# new_board.net
KiCad netlist of a schematic drawn in Altium Designer
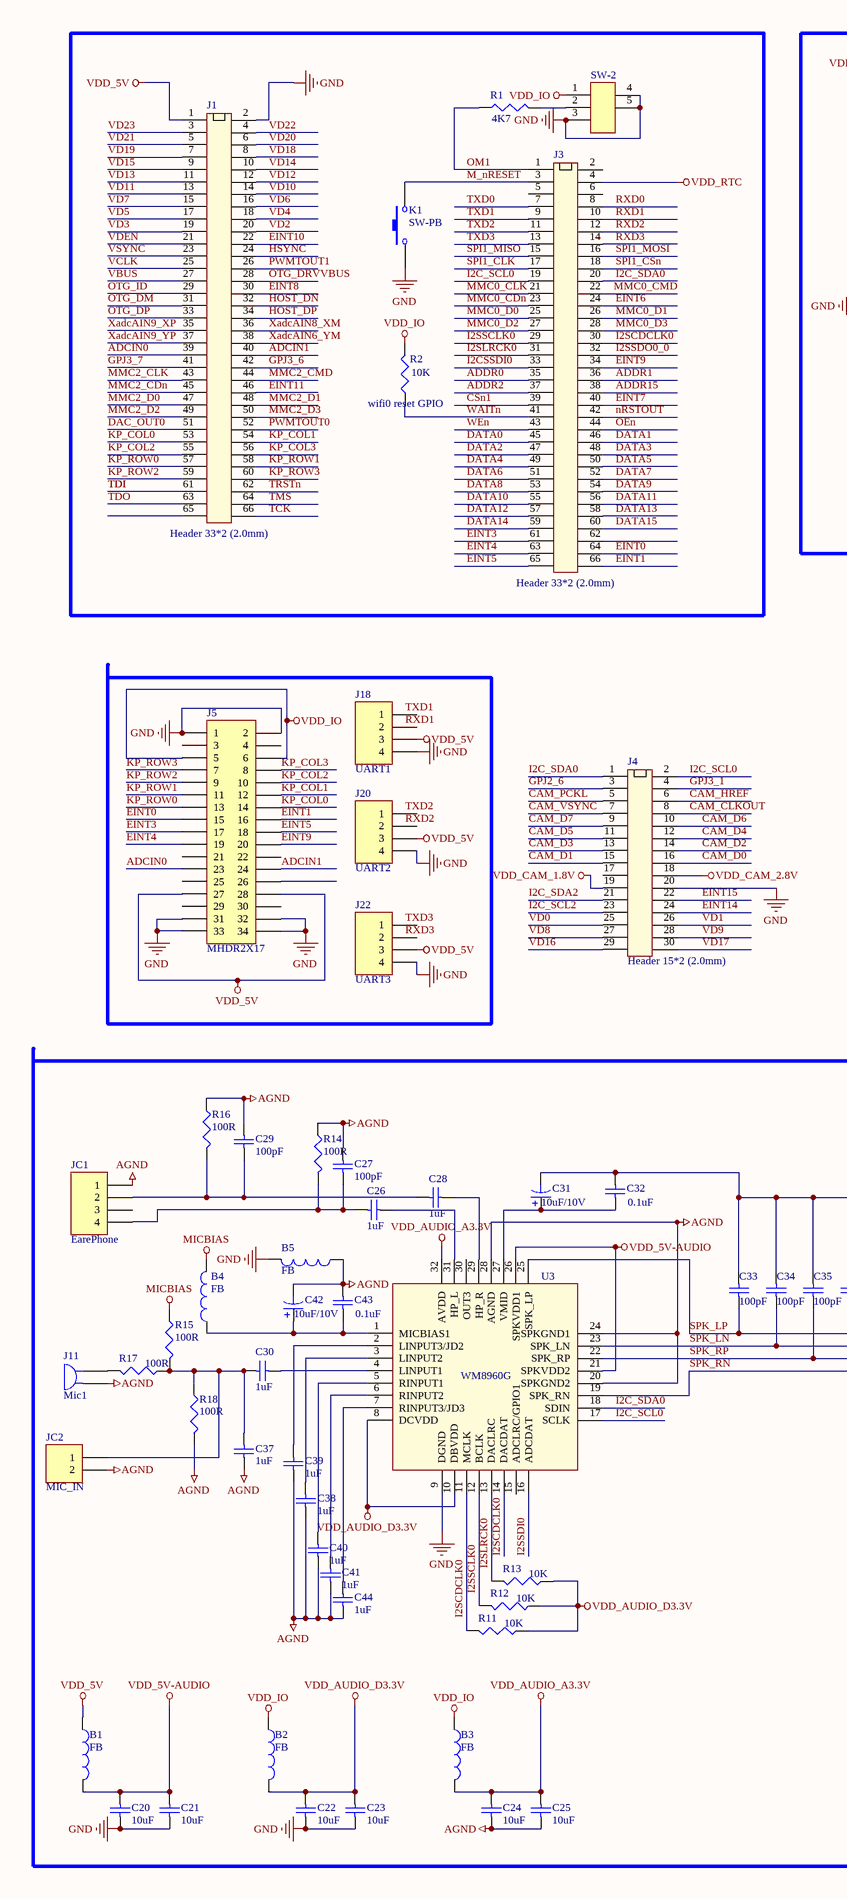
[diagram p0: new_board.SchDoc, left]
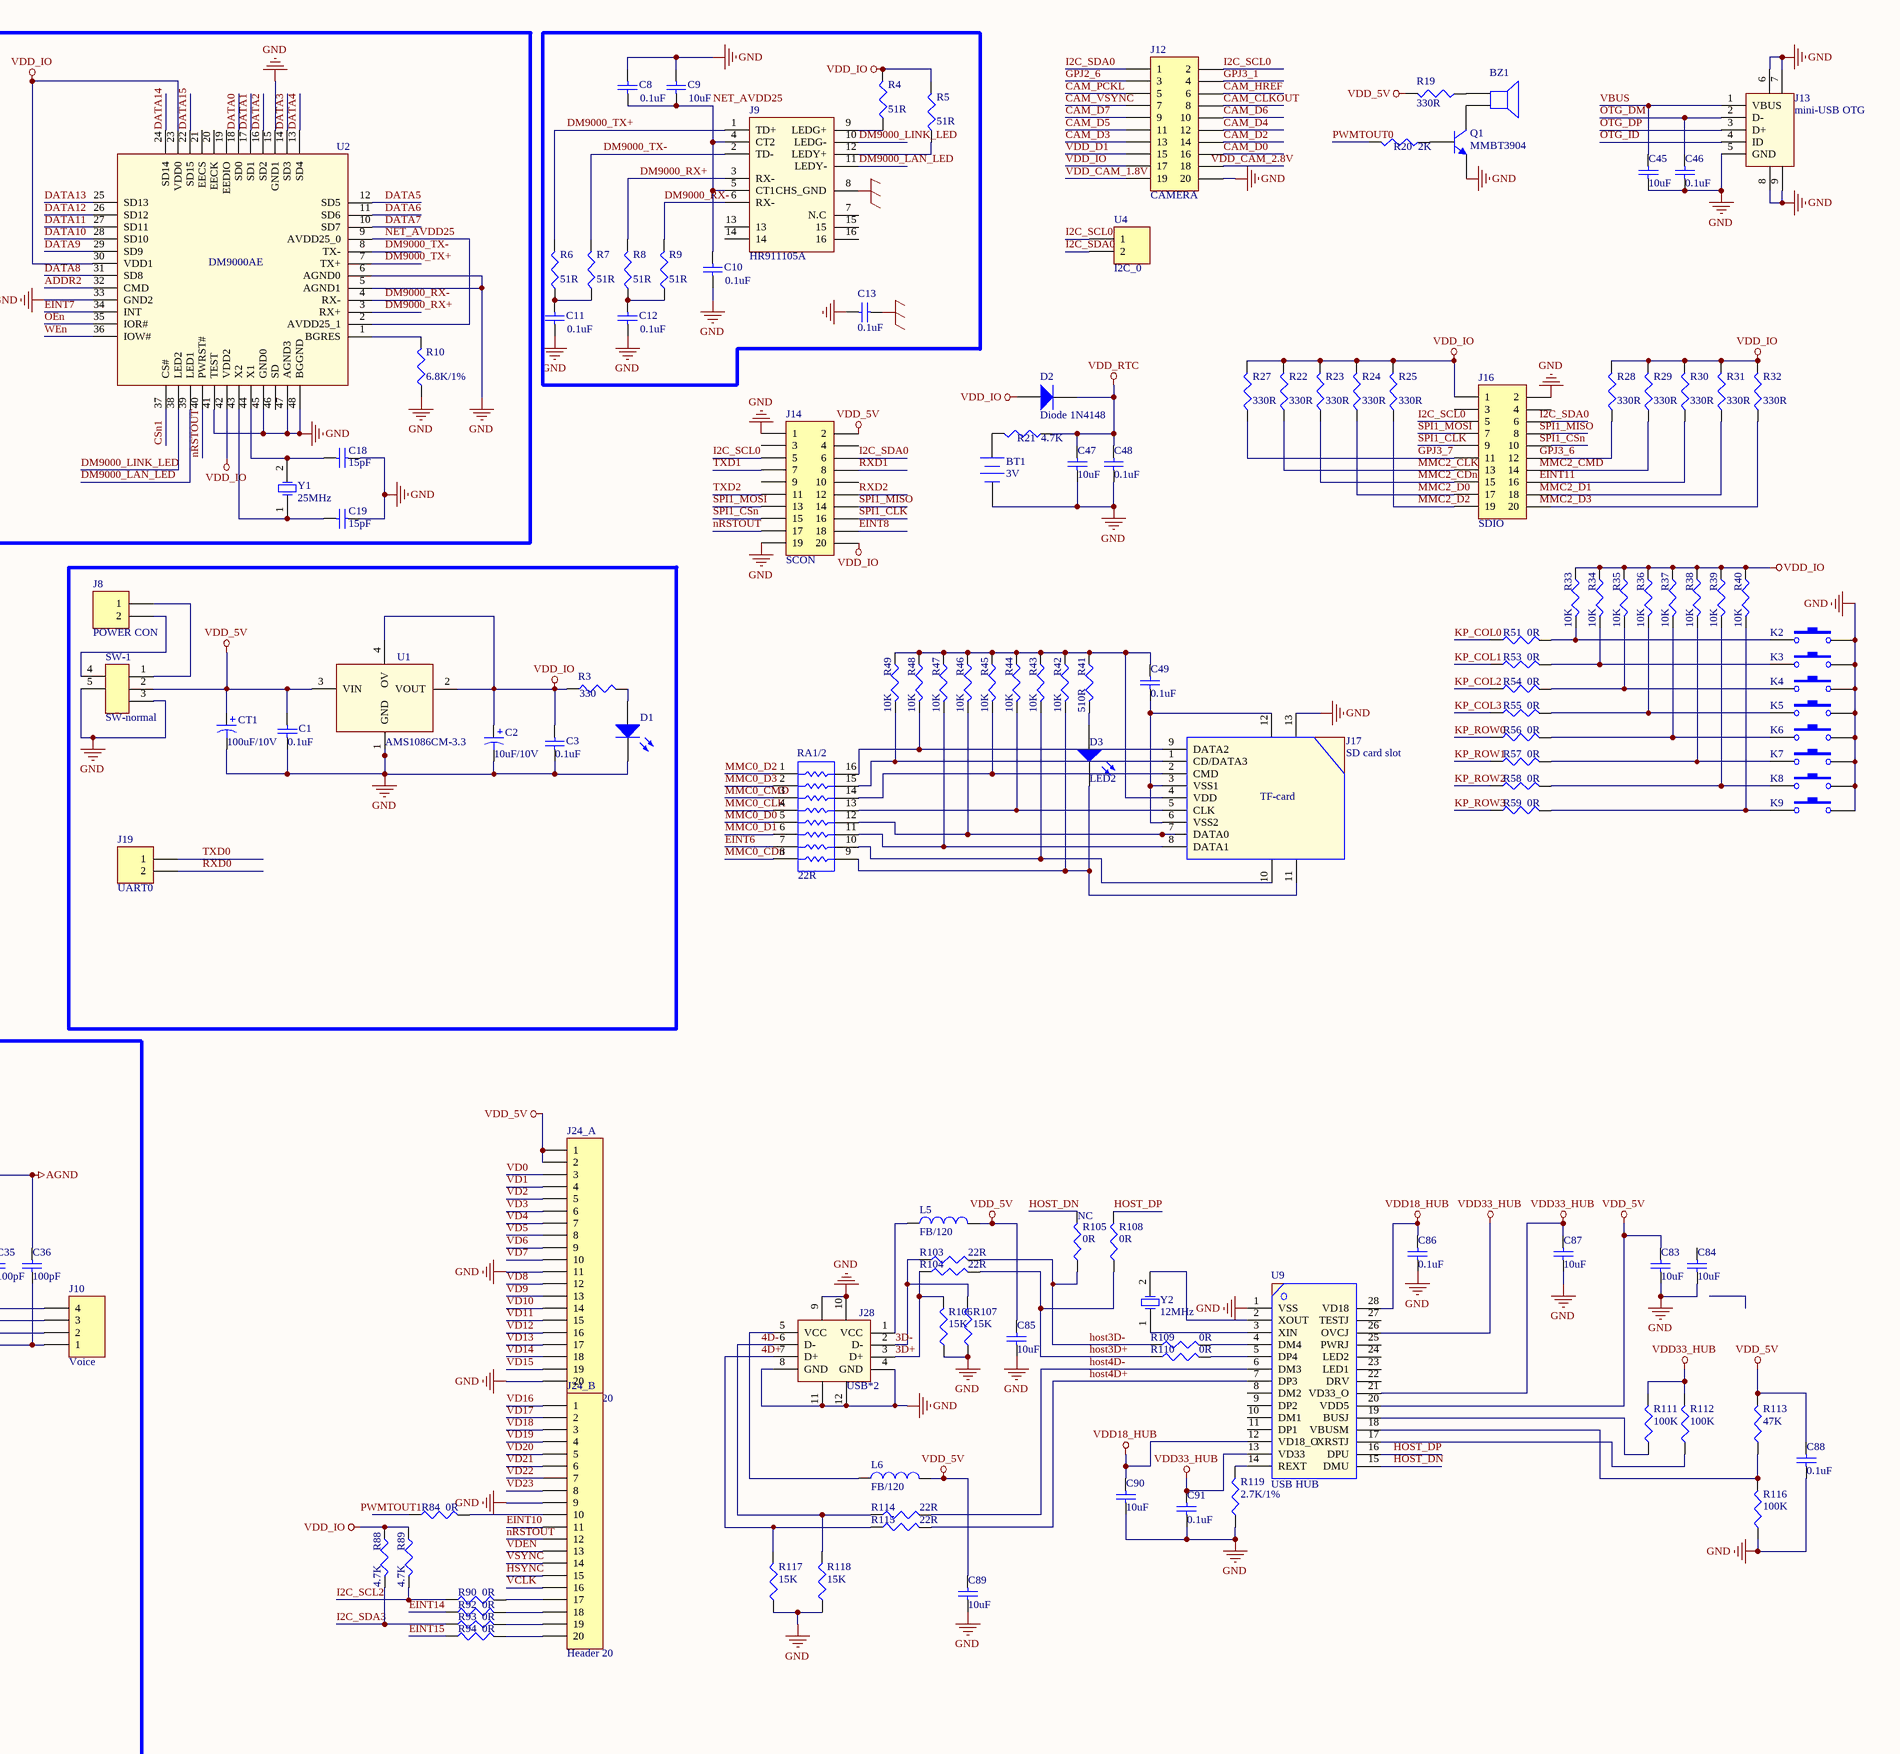
[diagram p1: new_board.SchDoc, right]

(export (version "E")
  (design (tool "Eeschema 10.0.6"))
  (components
    (comp (ref "B1")
      (value "FB")
      (footprint "0603")
      (description "Inductor")
      (fields (field (name "PUBLISHER") "Altium Limited"))
      (libsource (lib "Miscellaneous Devices") (part "Inductor"))
    )
    (comp (ref "B2")
      (value "FB")
      (footprint "0603")
      (description "Inductor")
      (fields (field (name "PUBLISHER") "Altium Limited"))
      (libsource (lib "Miscellaneous Devices") (part "Inductor"))
    )
    (comp (ref "B3")
      (value "FB")
      (footprint "0603")
      (description "Inductor")
      (fields (field (name "PUBLISHER") "Altium Limited"))
      (libsource (lib "Miscellaneous Devices") (part "Inductor"))
    )
    (comp (ref "B4")
      (value "FB")
      (footprint "0603")
      (description "Inductor")
      (fields (field (name "PUBLISHER") "Altium Limited"))
      (libsource (lib "Miscellaneous Devices") (part "Inductor"))
    )
    (comp (ref "B5")
      (value "FB")
      (footprint "0603")
      (description "Inductor")
      (fields (field (name "PUBLISHER") "Altium Limited"))
      (libsource (lib "Miscellaneous Devices") (part "Inductor"))
    )
    (comp (ref "BT1")
      (value "3V")
      (footprint "BAT-2")
      (description "Multicell Battery")
      (fields (field (name "PUBLISHER") "Altium Limited"))
      (libsource (lib "Miscellaneous Devices") (part "Battery"))
    )
    (comp (ref "BZ1")
      (value "Speaker")
      (footprint "PIN2")
      (description "Loudspeaker")
      (fields (field (name "PUBLISHER") "Altium Limited"))
      (libsource (lib "Miscellaneous Devices") (part "Speaker"))
    )
    (comp (ref "C1")
      (value "0.1uF")
      (footprint "1608[0603]")
      (description "Capacitor (Semiconductor SIM Model)")
      (fields (field (name "Comment") "Cap Semi") (field (name "PUBLISHER") "Altium Limited"))
      (libsource (lib "Miscellaneous Devices") (part "Cap Semi"))
    )
    (comp (ref "C2")
      (value "10uF/10V")
      (footprint "C0805")
      (description "Polarized Capacitor (Surface Mount)")
      (fields (field (name "Comment") "Cap Pol3") (field (name "PUBLISHER") "Altium Limited"))
      (libsource (lib "Miscellaneous Devices") (part "Cap Pol3"))
    )
    (comp (ref "C3")
      (value "0.1uF")
      (footprint "1608[0603]")
      (description "Capacitor (Semiconductor SIM Model)")
      (fields (field (name "Comment") "Cap Semi") (field (name "PUBLISHER") "Altium Limited"))
      (libsource (lib "Miscellaneous Devices") (part "Cap Semi"))
    )
    (comp (ref "C8")
      (value "0.1uF")
      (footprint "1608[0603]")
      (description "Capacitor (Semiconductor SIM Model)")
      (fields (field (name "Comment") "Cap Semi") (field (name "PUBLISHER") "Altium Limited"))
      (libsource (lib "Miscellaneous Devices") (part "Cap Semi"))
    )
    (comp (ref "C9")
      (value "10uF")
      (footprint "1608[0603]")
      (description "Capacitor (Semiconductor SIM Model)")
      (fields (field (name "Comment") "Cap Semi") (field (name "PUBLISHER") "Altium Limited"))
      (libsource (lib "Miscellaneous Devices") (part "Cap Semi"))
    )
    (comp (ref "C10")
      (value "0.1uF")
      (footprint "1608[0603]")
      (description "Capacitor (Semiconductor SIM Model)")
      (fields (field (name "Comment") "Cap Semi") (field (name "PUBLISHER") "Altium Limited"))
      (libsource (lib "Miscellaneous Devices") (part "Cap Semi"))
    )
    (comp (ref "C11")
      (value "0.1uF")
      (footprint "1608[0603]")
      (description "Capacitor (Semiconductor SIM Model)")
      (fields (field (name "Comment") "Cap Semi") (field (name "PUBLISHER") "Altium Limited"))
      (libsource (lib "Miscellaneous Devices") (part "Cap Semi"))
    )
    (comp (ref "C12")
      (value "0.1uF")
      (footprint "1608[0603]")
      (description "Capacitor (Semiconductor SIM Model)")
      (fields (field (name "Comment") "Cap Semi") (field (name "PUBLISHER") "Altium Limited"))
      (libsource (lib "Miscellaneous Devices") (part "Cap Semi"))
    )
    (comp (ref "C13")
      (value "0.1uF")
      (footprint "1608[0603]")
      (description "Capacitor (Semiconductor SIM Model)")
      (fields (field (name "Comment") "Cap Semi") (field (name "PUBLISHER") "Altium Limited"))
      (libsource (lib "Miscellaneous Devices") (part "Cap Semi"))
    )
    (comp (ref "C18")
      (value "15pF")
      (footprint "1608[0603]")
      (description "Capacitor (Semiconductor SIM Model)")
      (fields (field (name "Comment") "Cap Semi") (field (name "PUBLISHER") "Altium Limited"))
      (libsource (lib "Miscellaneous Devices") (part "Cap Semi"))
    )
    (comp (ref "C19")
      (value "15pF")
      (footprint "1608[0603]")
      (description "Capacitor (Semiconductor SIM Model)")
      (fields (field (name "Comment") "Cap Semi") (field (name "PUBLISHER") "Altium Limited"))
      (libsource (lib "Miscellaneous Devices") (part "Cap Semi"))
    )
    (comp (ref "C20")
      (value "10uF")
      (footprint "1608[0603]")
      (description "Capacitor (Semiconductor SIM Model)")
      (fields (field (name "Comment") "Cap Semi") (field (name "PUBLISHER") "Altium Limited"))
      (libsource (lib "Miscellaneous Devices") (part "Cap Semi"))
    )
    (comp (ref "C21")
      (value "10uF")
      (footprint "1608[0603]")
      (description "Capacitor (Semiconductor SIM Model)")
      (fields (field (name "Comment") "Cap Semi") (field (name "PUBLISHER") "Altium Limited"))
      (libsource (lib "Miscellaneous Devices") (part "Cap Semi"))
    )
    (comp (ref "C22")
      (value "10uF")
      (footprint "1608[0603]")
      (description "Capacitor (Semiconductor SIM Model)")
      (fields (field (name "Comment") "Cap Semi") (field (name "PUBLISHER") "Altium Limited"))
      (libsource (lib "Miscellaneous Devices") (part "Cap Semi"))
    )
    (comp (ref "C23")
      (value "10uF")
      (footprint "1608[0603]")
      (description "Capacitor (Semiconductor SIM Model)")
      (fields (field (name "Comment") "Cap Semi") (field (name "PUBLISHER") "Altium Limited"))
      (libsource (lib "Miscellaneous Devices") (part "Cap Semi"))
    )
    (comp (ref "C24")
      (value "10uF")
      (footprint "1608[0603]")
      (description "Capacitor (Semiconductor SIM Model)")
      (fields (field (name "Comment") "Cap Semi") (field (name "PUBLISHER") "Altium Limited"))
      (libsource (lib "Miscellaneous Devices") (part "Cap Semi"))
    )
    (comp (ref "C25")
      (value "10uF")
      (footprint "1608[0603]")
      (description "Capacitor (Semiconductor SIM Model)")
      (fields (field (name "Comment") "Cap Semi") (field (name "PUBLISHER") "Altium Limited"))
      (libsource (lib "Miscellaneous Devices") (part "Cap Semi"))
    )
    (comp (ref "C26")
      (value "1uF")
      (footprint "1608[0603]")
      (description "Capacitor (Semiconductor SIM Model)")
      (fields (field (name "Comment") "Cap Semi") (field (name "PUBLISHER") "Altium Limited"))
      (libsource (lib "Miscellaneous Devices") (part "Cap Semi"))
    )
    (comp (ref "C27")
      (value "100pF")
      (footprint "1608[0603]")
      (description "Capacitor (Semiconductor SIM Model)")
      (fields (field (name "Comment") "Cap Semi") (field (name "PUBLISHER") "Altium Limited"))
      (libsource (lib "Miscellaneous Devices") (part "Cap Semi"))
    )
    (comp (ref "C28")
      (value "1uF")
      (footprint "1608[0603]")
      (description "Capacitor (Semiconductor SIM Model)")
      (fields (field (name "Comment") "Cap Semi") (field (name "PUBLISHER") "Altium Limited"))
      (libsource (lib "Miscellaneous Devices") (part "Cap Semi"))
    )
    (comp (ref "C29")
      (value "100pF")
      (footprint "1608[0603]")
      (description "Capacitor (Semiconductor SIM Model)")
      (fields (field (name "Comment") "Cap Semi") (field (name "PUBLISHER") "Altium Limited"))
      (libsource (lib "Miscellaneous Devices") (part "Cap Semi"))
    )
    (comp (ref "C30")
      (value "1uF")
      (footprint "1608[0603]")
      (description "Capacitor (Semiconductor SIM Model)")
      (fields (field (name "Comment") "Cap Semi") (field (name "PUBLISHER") "Altium Limited"))
      (libsource (lib "Miscellaneous Devices") (part "Cap Semi"))
    )
    (comp (ref "C31")
      (value "10uF/10V")
      (footprint "C0805")
      (description "Polarized Capacitor (Surface Mount)")
      (fields (field (name "Comment") "Cap Pol3") (field (name "PUBLISHER") "Altium Limited"))
      (libsource (lib "Miscellaneous Devices") (part "Cap Pol3"))
    )
    (comp (ref "C32")
      (value "0.1uF")
      (footprint "1608[0603]")
      (description "Capacitor (Semiconductor SIM Model)")
      (fields (field (name "Comment") "Cap Semi") (field (name "PUBLISHER") "Altium Limited"))
      (libsource (lib "Miscellaneous Devices") (part "Cap Semi"))
    )
    (comp (ref "C33")
      (value "100pF")
      (footprint "1608[0603]")
      (description "Capacitor (Semiconductor SIM Model)")
      (fields (field (name "Comment") "Cap Semi") (field (name "PUBLISHER") "Altium Limited"))
      (libsource (lib "Miscellaneous Devices") (part "Cap Semi"))
    )
    (comp (ref "C34")
      (value "100pF")
      (footprint "1608[0603]")
      (description "Capacitor (Semiconductor SIM Model)")
      (fields (field (name "Comment") "Cap Semi") (field (name "PUBLISHER") "Altium Limited"))
      (libsource (lib "Miscellaneous Devices") (part "Cap Semi"))
    )
    (comp (ref "C35")
      (value "100pF")
      (footprint "1608[0603]")
      (description "Capacitor (Semiconductor SIM Model)")
      (fields (field (name "Comment") "Cap Semi") (field (name "PUBLISHER") "Altium Limited"))
      (libsource (lib "Miscellaneous Devices") (part "Cap Semi"))
    )
    (comp (ref "C36")
      (value "100pF")
      (footprint "1608[0603]")
      (description "Capacitor (Semiconductor SIM Model)")
      (fields (field (name "Comment") "Cap Semi") (field (name "PUBLISHER") "Altium Limited"))
      (libsource (lib "Miscellaneous Devices") (part "Cap Semi"))
    )
    (comp (ref "C37")
      (value "1uF")
      (footprint "1608[0603]")
      (description "Capacitor (Semiconductor SIM Model)")
      (fields (field (name "Comment") "Cap Semi") (field (name "PUBLISHER") "Altium Limited"))
      (libsource (lib "Miscellaneous Devices") (part "Cap Semi"))
    )
    (comp (ref "C38")
      (value "1uF")
      (footprint "1608[0603]")
      (description "Capacitor (Semiconductor SIM Model)")
      (fields (field (name "Comment") "Cap Semi") (field (name "PUBLISHER") "Altium Limited"))
      (libsource (lib "Miscellaneous Devices") (part "Cap Semi"))
    )
    (comp (ref "C39")
      (value "1uF")
      (footprint "1608[0603]")
      (description "Capacitor (Semiconductor SIM Model)")
      (fields (field (name "Comment") "Cap Semi") (field (name "PUBLISHER") "Altium Limited"))
      (libsource (lib "Miscellaneous Devices") (part "Cap Semi"))
    )
    (comp (ref "C40")
      (value "1uF")
      (footprint "1608[0603]")
      (description "Capacitor (Semiconductor SIM Model)")
      (fields (field (name "Comment") "Cap Semi") (field (name "PUBLISHER") "Altium Limited"))
      (libsource (lib "Miscellaneous Devices") (part "Cap Semi"))
    )
    (comp (ref "C41")
      (value "1uF")
      (footprint "1608[0603]")
      (description "Capacitor (Semiconductor SIM Model)")
      (fields (field (name "Comment") "Cap Semi") (field (name "PUBLISHER") "Altium Limited"))
      (libsource (lib "Miscellaneous Devices") (part "Cap Semi"))
    )
    (comp (ref "C42")
      (value "10uF/10V")
      (footprint "C0805")
      (description "Polarized Capacitor (Surface Mount)")
      (fields (field (name "Comment") "Cap Pol3") (field (name "PUBLISHER") "Altium Limited"))
      (libsource (lib "Miscellaneous Devices") (part "Cap Pol3"))
    )
    (comp (ref "C43")
      (value "0.1uF")
      (footprint "1608[0603]")
      (description "Capacitor (Semiconductor SIM Model)")
      (fields (field (name "Comment") "Cap Semi") (field (name "PUBLISHER") "Altium Limited"))
      (libsource (lib "Miscellaneous Devices") (part "Cap Semi"))
    )
    (comp (ref "C44")
      (value "1uF")
      (footprint "1608[0603]")
      (description "Capacitor (Semiconductor SIM Model)")
      (fields (field (name "Comment") "Cap Semi") (field (name "PUBLISHER") "Altium Limited"))
      (libsource (lib "Miscellaneous Devices") (part "Cap Semi"))
    )
    (comp (ref "C45")
      (value "10uF")
      (footprint "1608[0603]")
      (description "Capacitor (Semiconductor SIM Model)")
      (fields (field (name "Comment") "Cap Semi") (field (name "PUBLISHER") "Altium Limited"))
      (libsource (lib "Miscellaneous Devices") (part "Cap Semi"))
    )
    (comp (ref "C46")
      (value "0.1uF")
      (footprint "1608[0603]")
      (description "Capacitor (Semiconductor SIM Model)")
      (fields (field (name "Comment") "Cap Semi") (field (name "PUBLISHER") "Altium Limited"))
      (libsource (lib "Miscellaneous Devices") (part "Cap Semi"))
    )
    (comp (ref "C47")
      (value "10uF")
      (footprint "1608[0603]")
      (description "Capacitor (Semiconductor SIM Model)")
      (fields (field (name "Comment") "Cap Semi") (field (name "PUBLISHER") "Altium Limited"))
      (libsource (lib "Miscellaneous Devices") (part "Cap Semi"))
    )
    (comp (ref "C48")
      (value "0.1uF")
      (footprint "1608[0603]")
      (description "Capacitor (Semiconductor SIM Model)")
      (fields (field (name "Comment") "Cap Semi") (field (name "PUBLISHER") "Altium Limited"))
      (libsource (lib "Miscellaneous Devices") (part "Cap Semi"))
    )
    (comp (ref "C49")
      (value "0.1uF")
      (footprint "1608[0603]")
      (description "Capacitor (Semiconductor SIM Model)")
      (fields (field (name "Comment") "Cap Semi") (field (name "PUBLISHER") "Altium Limited"))
      (libsource (lib "Miscellaneous Devices") (part "Cap Semi"))
    )
    (comp (ref "C83")
      (value "10uF")
      (footprint "1608[0603]")
      (description "Capacitor (Semiconductor SIM Model)")
      (fields (field (name "Comment") "Cap Semi") (field (name "PUBLISHER") "Altium Limited"))
      (libsource (lib "Miscellaneous Devices") (part "Cap Semi"))
    )
    (comp (ref "C84")
      (value "10uF")
      (footprint "1608[0603]")
      (description "Capacitor (Semiconductor SIM Model)")
      (fields (field (name "Comment") "Cap Semi") (field (name "PUBLISHER") "Altium Limited"))
      (libsource (lib "Miscellaneous Devices") (part "Cap Semi"))
    )
    (comp (ref "C85")
      (value "10uF")
      (footprint "1608[0603]")
      (description "Capacitor (Semiconductor SIM Model)")
      (fields (field (name "Comment") "Cap Semi") (field (name "PUBLISHER") "Altium Limited"))
      (libsource (lib "Miscellaneous Devices") (part "Cap Semi"))
    )
    (comp (ref "C86")
      (value "0.1uF")
      (footprint "1608[0603]")
      (description "Capacitor (Semiconductor SIM Model)")
      (fields (field (name "Comment") "Cap Semi") (field (name "PUBLISHER") "Altium Limited"))
      (libsource (lib "Miscellaneous Devices") (part "Cap Semi"))
    )
    (comp (ref "C87")
      (value "10uF")
      (footprint "1608[0603]")
      (description "Capacitor (Semiconductor SIM Model)")
      (fields (field (name "Comment") "Cap Semi") (field (name "PUBLISHER") "Altium Limited"))
      (libsource (lib "Miscellaneous Devices") (part "Cap Semi"))
    )
    (comp (ref "C88")
      (value "0.1uF")
      (footprint "1608[0603]")
      (description "Capacitor (Semiconductor SIM Model)")
      (fields (field (name "Comment") "Cap Semi") (field (name "PUBLISHER") "Altium Limited"))
      (libsource (lib "Miscellaneous Devices") (part "Cap Semi"))
    )
    (comp (ref "C89")
      (value "10uF")
      (footprint "1608[0603]")
      (description "Capacitor (Semiconductor SIM Model)")
      (fields (field (name "Comment") "Cap Semi") (field (name "PUBLISHER") "Altium Limited"))
      (libsource (lib "Miscellaneous Devices") (part "Cap Semi"))
    )
    (comp (ref "C90")
      (value "10uF")
      (footprint "1608[0603]")
      (description "Capacitor (Semiconductor SIM Model)")
      (fields (field (name "Comment") "Cap Semi") (field (name "PUBLISHER") "Altium Limited"))
      (libsource (lib "Miscellaneous Devices") (part "Cap Semi"))
    )
    (comp (ref "C91")
      (value "0.1uF")
      (footprint "1608[0603]")
      (description "Capacitor (Semiconductor SIM Model)")
      (fields (field (name "Comment") "Cap Semi") (field (name "PUBLISHER") "Altium Limited"))
      (libsource (lib "Miscellaneous Devices") (part "Cap Semi"))
    )
    (comp (ref "CT1")
      (value "100uF/10V")
      (footprint "C0805")
      (description "Polarized Capacitor (Surface Mount)")
      (fields (field (name "Comment") "Cap Pol3") (field (name "PUBLISHER") "Altium Limited"))
      (libsource (lib "Miscellaneous Devices") (part "Cap Pol3"))
    )
    (comp (ref "D1")
      (value "LED1")
      (footprint "3.2X1.6X1.1")
      (description "Typical RED, GREEN, YELLOW, AMBER GaAs LED")
      (fields (field (name "PUBLISHER") "Altium Limited"))
      (libsource (lib "Miscellaneous Devices") (part "LED2"))
    )
    (comp (ref "D2")
      (value "Diode 1N4148")
      (footprint "DO-35")
      (description "High Conductance Fast Diode")
      (fields (field (name "PUBLISHER") "Altium Limited"))
      (libsource (lib "Miscellaneous Devices") (part "Diode 1N4148"))
    )
    (comp (ref "D3")
      (value "LED2")
      (footprint "3.2X1.6X1.1")
      (description "Typical RED, GREEN, YELLOW, AMBER GaAs LED")
      (fields (field (name "PUBLISHER") "Altium Limited"))
      (libsource (lib "Miscellaneous Devices") (part "LED2"))
    )
    (comp (ref "J1") (value "Header 33*2 (2.0mm)") (libsource (lib "Schlib") (part "Header 33*2 (2.0mm)")))
    (comp (ref "J3") (value "Header 33*2 (2.0mm)") (libsource (lib "Schlib") (part "Header 33*2 (2.0mm)")))
    (comp (ref "J4") (value "Header 15*2 (2.0mm)") (libsource (lib "Schlib") (part "Header 15*2 (2.0mm)")))
    (comp (ref "J5")
      (value "MHDR2X17")
      (footprint "MHDR2X17")
      (description "Header, 17-Pin, Dual row")
      (fields (field (name "PUBLISHER") "Altium Limited"))
      (libsource (lib "Miscellaneous Connectors") (part "MHDR2X17"))
    )
    (comp (ref "J8")
      (value "POWER CON")
      (footprint "HDR1X2H")
      (description "Header, 2-Pin, Right Angle")
      (fields (field (name "PUBLISHER") "Altium Limited"))
      (libsource (lib "Miscellaneous Connectors") (part "Header 2H"))
    )
    (comp (ref "J9")
      (value "HR911105A")
      (description "100M net connector")
      (libsource (lib "Schlib") (part "HR911105A"))
    )
    (comp (ref "J10")
      (value "Voice")
      (footprint "HDR1X4")
      (description "Header, 4-Pin")
      (fields (field (name "PUBLISHER") "Altium Limited"))
      (libsource (lib "") (part "Header 4_1"))
    )
    (comp (ref "J11")
      (value "Mic1")
      (footprint "PIN2")
      (description "Microphone")
      (fields (field (name "PUBLISHER") "Altium Limited"))
      (libsource (lib "Miscellaneous Devices") (part "Mic1"))
    )
    (comp (ref "J12")
      (value "CAMERA")
      (footprint "HDR2X10")
      (description "Header, 10-Pin, Dual row")
      (fields (field (name "PUBLISHER") "Altium Limited"))
      (libsource (lib "Miscellaneous Connectors") (part "Header 10X2"))
    )
    (comp (ref "J13") (value "mini-USB OTG") (libsource (lib "Schlib") (part "mini-USB OTG")))
    (comp (ref "J14")
      (value "SCON")
      (footprint "HDR2X10")
      (description "Header, 10-Pin, Dual row")
      (fields (field (name "PUBLISHER") "Altium Limited"))
      (libsource (lib "Miscellaneous Connectors") (part "Header 10X2"))
    )
    (comp (ref "J16")
      (value "SDIO")
      (footprint "HDR2X10")
      (description "Header, 10-Pin, Dual row")
      (fields (field (name "PUBLISHER") "Altium Limited"))
      (libsource (lib "Miscellaneous Connectors") (part "Header 10X2"))
    )
    (comp (ref "J17") (value "SD card slot") (libsource (lib "Schlib") (part "SD card slot")))
    (comp (ref "J18")
      (value "UART1")
      (footprint "MHDR1X4")
      (description "Header, 4-Pin")
      (fields (field (name "PUBLISHER") "Altium Limited"))
      (libsource (lib "Miscellaneous Connectors") (part "MHDR1X4"))
    )
    (comp (ref "J19")
      (value "UART0")
      (footprint "HDR1X2H")
      (description "Header, 2-Pin, Right Angle")
      (fields (field (name "PUBLISHER") "Altium Limited"))
      (libsource (lib "Miscellaneous Connectors") (part "Header 2H"))
    )
    (comp (ref "J20")
      (value "UART2")
      (footprint "MHDR1X4")
      (description "Header, 4-Pin")
      (fields (field (name "PUBLISHER") "Altium Limited"))
      (libsource (lib "Miscellaneous Connectors") (part "MHDR1X4"))
    )
    (comp (ref "J22")
      (value "UART3")
      (footprint "MHDR1X4")
      (description "Header, 4-Pin")
      (fields (field (name "PUBLISHER") "Altium Limited"))
      (libsource (lib "Miscellaneous Connectors") (part "MHDR1X4"))
    )
    (comp (ref "J24_A")
      (value "Header 20")
      (footprint "HDR1X20")
      (description "Header, 20-Pin")
      (fields (field (name "PUBLISHER") "Altium Limited"))
      (libsource (lib "Miscellaneous Connectors") (part "Header 20"))
    )
    (comp (ref "J24_B")
      (value "Header 20")
      (footprint "HDR1X20")
      (description "Header, 20-Pin")
      (fields (field (name "PUBLISHER") "Altium Limited"))
      (libsource (lib "Miscellaneous Connectors") (part "Header 20"))
    )
    (comp (ref "J28") (value "USB*2") (libsource (lib "Schlib") (part "USB*2")))
    (comp (ref "JC1")
      (value "EarePhone")
      (footprint "HDR1X4")
      (description "Header, 4-Pin")
      (fields (field (name "PUBLISHER") "Altium Limited"))
      (libsource (lib "Miscellaneous Connectors") (part "Header 4"))
    )
    (comp (ref "JC2")
      (value "MIC_IN")
      (footprint "HDR1X2")
      (description "Header, 2-Pin")
      (fields (field (name "PUBLISHER") "Altium Limited"))
      (libsource (lib "") (part "Header 2_1"))
    )
    (comp (ref "K1")
      (value "SW-PB")
      (footprint "SPST-2")
      (description "Switch")
      (fields (field (name "PUBLISHER") "Altium Limited"))
      (libsource (lib "Miscellaneous Devices") (part "SW-PB"))
    )
    (comp (ref "K2")
      (value "SW-PB")
      (footprint "SPST-2")
      (description "Switch")
      (fields (field (name "PUBLISHER") "Altium Limited"))
      (libsource (lib "Miscellaneous Devices") (part "SW-PB"))
    )
    (comp (ref "K3")
      (value "SW-PB")
      (footprint "SPST-2")
      (description "Switch")
      (fields (field (name "PUBLISHER") "Altium Limited"))
      (libsource (lib "Miscellaneous Devices") (part "SW-PB"))
    )
    (comp (ref "K4")
      (value "SW-PB")
      (footprint "SPST-2")
      (description "Switch")
      (fields (field (name "PUBLISHER") "Altium Limited"))
      (libsource (lib "Miscellaneous Devices") (part "SW-PB"))
    )
    (comp (ref "K5")
      (value "SW-PB")
      (footprint "SPST-2")
      (description "Switch")
      (fields (field (name "PUBLISHER") "Altium Limited"))
      (libsource (lib "Miscellaneous Devices") (part "SW-PB"))
    )
    (comp (ref "K6")
      (value "SW-PB")
      (footprint "SPST-2")
      (description "Switch")
      (fields (field (name "PUBLISHER") "Altium Limited"))
      (libsource (lib "Miscellaneous Devices") (part "SW-PB"))
    )
    (comp (ref "K7")
      (value "SW-PB")
      (footprint "SPST-2")
      (description "Switch")
      (fields (field (name "PUBLISHER") "Altium Limited"))
      (libsource (lib "Miscellaneous Devices") (part "SW-PB"))
    )
    (comp (ref "K8")
      (value "SW-PB")
      (footprint "SPST-2")
      (description "Switch")
      (fields (field (name "PUBLISHER") "Altium Limited"))
      (libsource (lib "Miscellaneous Devices") (part "SW-PB"))
    )
    (comp (ref "K9")
      (value "SW-PB")
      (footprint "SPST-2")
      (description "Switch")
      (fields (field (name "PUBLISHER") "Altium Limited"))
      (libsource (lib "Miscellaneous Devices") (part "SW-PB"))
    )
    (comp (ref "L5")
      (value "FB/120")
      (footprint "0603")
      (description "Inductor")
      (fields (field (name "PUBLISHER") "Altium Limited"))
      (libsource (lib "Miscellaneous Devices") (part "Inductor"))
    )
    (comp (ref "L6")
      (value "FB/120")
      (footprint "0603")
      (description "Inductor")
      (fields (field (name "PUBLISHER") "Altium Limited"))
      (libsource (lib "Miscellaneous Devices") (part "Inductor"))
    )
    (comp (ref "Q1")
      (value "MMBT3904")
      (footprint "SOT-23B_N")
      (description "NPN Bipolar Transistor")
      (fields (field (name "PUBLISHER") "Altium Limited"))
      (libsource (lib "Miscellaneous Devices") (part "QNPN"))
    )
    (comp (ref "R1")
      (value "4K7")
      (footprint "J1-0603")
      (description "Resistor")
      (fields (field (name "Comment") "Res3") (field (name "PUBLISHER") "Altium Limited"))
      (libsource (lib "Miscellaneous Devices") (part "Res3"))
    )
    (comp (ref "R2")
      (value "10K")
      (footprint "J1-0603")
      (description "Resistor")
      (fields (field (name "Comment") "Res3") (field (name "PUBLISHER") "Altium Limited"))
      (libsource (lib "Miscellaneous Devices") (part "Res3"))
    )
    (comp (ref "R3")
      (value "330")
      (footprint "J1-0603")
      (description "Resistor")
      (fields (field (name "Comment") "Res3") (field (name "PUBLISHER") "Altium Limited"))
      (libsource (lib "Miscellaneous Devices") (part "Res3"))
    )
    (comp (ref "R4")
      (value "51R")
      (footprint "J1-0603")
      (description "Resistor")
      (fields (field (name "Comment") "Res3") (field (name "PUBLISHER") "Altium Limited"))
      (libsource (lib "Miscellaneous Devices") (part "Res3"))
    )
    (comp (ref "R5")
      (value "51R")
      (footprint "J1-0603")
      (description "Resistor")
      (fields (field (name "Comment") "Res3") (field (name "PUBLISHER") "Altium Limited"))
      (libsource (lib "Miscellaneous Devices") (part "Res3"))
    )
    (comp (ref "R6")
      (value "51R")
      (footprint "J1-0603")
      (description "Resistor")
      (fields (field (name "Comment") "Res3") (field (name "PUBLISHER") "Altium Limited"))
      (libsource (lib "Miscellaneous Devices") (part "Res3"))
    )
    (comp (ref "R7")
      (value "51R")
      (footprint "J1-0603")
      (description "Resistor")
      (fields (field (name "Comment") "Res3") (field (name "PUBLISHER") "Altium Limited"))
      (libsource (lib "Miscellaneous Devices") (part "Res3"))
    )
    (comp (ref "R8")
      (value "51R")
      (footprint "J1-0603")
      (description "Resistor")
      (fields (field (name "Comment") "Res3") (field (name "PUBLISHER") "Altium Limited"))
      (libsource (lib "Miscellaneous Devices") (part "Res3"))
    )
    (comp (ref "R9")
      (value "51R")
      (footprint "J1-0603")
      (description "Resistor")
      (fields (field (name "Comment") "Res3") (field (name "PUBLISHER") "Altium Limited"))
      (libsource (lib "Miscellaneous Devices") (part "Res3"))
    )
    (comp (ref "R10")
      (value "6.8K/1%")
      (footprint "J1-0603")
      (description "Resistor")
      (fields (field (name "Comment") "Res3") (field (name "PUBLISHER") "Altium Limited"))
      (libsource (lib "Miscellaneous Devices") (part "Res3"))
    )
    (comp (ref "R11")
      (value "10K")
      (footprint "J1-0603")
      (description "Resistor")
      (fields (field (name "Comment") "Res3") (field (name "PUBLISHER") "Altium Limited"))
      (libsource (lib "Miscellaneous Devices") (part "Res3"))
    )
    (comp (ref "R12")
      (value "10K")
      (footprint "J1-0603")
      (description "Resistor")
      (fields (field (name "Comment") "Res3") (field (name "PUBLISHER") "Altium Limited"))
      (libsource (lib "Miscellaneous Devices") (part "Res3"))
    )
    (comp (ref "R13")
      (value "10K")
      (footprint "J1-0603")
      (description "Resistor")
      (fields (field (name "Comment") "Res3") (field (name "PUBLISHER") "Altium Limited"))
      (libsource (lib "Miscellaneous Devices") (part "Res3"))
    )
    (comp (ref "R14")
      (value "100R")
      (footprint "J1-0603")
      (description "Resistor")
      (fields (field (name "Comment") "Res3") (field (name "PUBLISHER") "Altium Limited"))
      (libsource (lib "Miscellaneous Devices") (part "Res3"))
    )
    (comp (ref "R15")
      (value "100R")
      (footprint "J1-0603")
      (description "Resistor")
      (fields (field (name "Comment") "Res3") (field (name "PUBLISHER") "Altium Limited"))
      (libsource (lib "Miscellaneous Devices") (part "Res3"))
    )
    (comp (ref "R16")
      (value "100R")
      (footprint "J1-0603")
      (description "Resistor")
      (fields (field (name "Comment") "Res3") (field (name "PUBLISHER") "Altium Limited"))
      (libsource (lib "Miscellaneous Devices") (part "Res3"))
    )
    (comp (ref "R17")
      (value "100R")
      (footprint "J1-0603")
      (description "Resistor")
      (fields (field (name "Comment") "Res3") (field (name "PUBLISHER") "Altium Limited"))
      (libsource (lib "Miscellaneous Devices") (part "Res3"))
    )
    (comp (ref "R18")
      (value "100R")
      (footprint "J1-0603")
      (description "Resistor")
      (fields (field (name "Comment") "Res3") (field (name "PUBLISHER") "Altium Limited"))
      (libsource (lib "Miscellaneous Devices") (part "Res3"))
    )
    (comp (ref "R19")
      (value "330R")
      (footprint "J1-0603")
      (description "Resistor")
      (fields (field (name "Comment") "Res3") (field (name "PUBLISHER") "Altium Limited"))
      (libsource (lib "Miscellaneous Devices") (part "Res3"))
    )
    (comp (ref "R20")
      (value "2K")
      (footprint "J1-0603")
      (description "Resistor")
      (fields (field (name "Comment") "Res3") (field (name "PUBLISHER") "Altium Limited"))
      (libsource (lib "Miscellaneous Devices") (part "Res3"))
    )
    (comp (ref "R21")
      (value "4.7K")
      (footprint "J1-0603")
      (description "Resistor")
      (fields (field (name "Comment") "Res3") (field (name "PUBLISHER") "Altium Limited"))
      (libsource (lib "Miscellaneous Devices") (part "Res3"))
    )
    (comp (ref "R22")
      (value "330R")
      (footprint "J1-0603")
      (description "Resistor")
      (fields (field (name "Comment") "Res3") (field (name "PUBLISHER") "Altium Limited"))
      (libsource (lib "Miscellaneous Devices") (part "Res3"))
    )
    (comp (ref "R23")
      (value "330R")
      (footprint "J1-0603")
      (description "Resistor")
      (fields (field (name "Comment") "Res3") (field (name "PUBLISHER") "Altium Limited"))
      (libsource (lib "Miscellaneous Devices") (part "Res3"))
    )
    (comp (ref "R24")
      (value "330R")
      (footprint "J1-0603")
      (description "Resistor")
      (fields (field (name "Comment") "Res3") (field (name "PUBLISHER") "Altium Limited"))
      (libsource (lib "Miscellaneous Devices") (part "Res3"))
    )
    (comp (ref "R25")
      (value "330R")
      (footprint "J1-0603")
      (description "Resistor")
      (fields (field (name "Comment") "Res3") (field (name "PUBLISHER") "Altium Limited"))
      (libsource (lib "Miscellaneous Devices") (part "Res3"))
    )
    (comp (ref "R27")
      (value "330R")
      (footprint "J1-0603")
      (description "Resistor")
      (fields (field (name "Comment") "Res3") (field (name "PUBLISHER") "Altium Limited"))
      (libsource (lib "Miscellaneous Devices") (part "Res3"))
    )
    (comp (ref "R28")
      (value "330R")
      (footprint "J1-0603")
      (description "Resistor")
      (fields (field (name "Comment") "Res3") (field (name "PUBLISHER") "Altium Limited"))
      (libsource (lib "Miscellaneous Devices") (part "Res3"))
    )
    (comp (ref "R29")
      (value "330R")
      (footprint "J1-0603")
      (description "Resistor")
      (fields (field (name "Comment") "Res3") (field (name "PUBLISHER") "Altium Limited"))
      (libsource (lib "Miscellaneous Devices") (part "Res3"))
    )
    (comp (ref "R30")
      (value "330R")
      (footprint "J1-0603")
      (description "Resistor")
      (fields (field (name "Comment") "Res3") (field (name "PUBLISHER") "Altium Limited"))
      (libsource (lib "Miscellaneous Devices") (part "Res3"))
    )
    (comp (ref "R31")
      (value "330R")
      (footprint "J1-0603")
      (description "Resistor")
      (fields (field (name "Comment") "Res3") (field (name "PUBLISHER") "Altium Limited"))
      (libsource (lib "Miscellaneous Devices") (part "Res3"))
    )
    (comp (ref "R32")
      (value "330R")
      (footprint "J1-0603")
      (description "Resistor")
      (fields (field (name "Comment") "Res3") (field (name "PUBLISHER") "Altium Limited"))
      (libsource (lib "Miscellaneous Devices") (part "Res3"))
    )
    (comp (ref "R33")
      (value "10K")
      (footprint "J1-0603")
      (description "Resistor")
      (fields (field (name "Comment") "Res3") (field (name "PUBLISHER") "Altium Limited"))
      (libsource (lib "Miscellaneous Devices") (part "Res3"))
    )
    (comp (ref "R34")
      (value "10K")
      (footprint "J1-0603")
      (description "Resistor")
      (fields (field (name "Comment") "Res3") (field (name "PUBLISHER") "Altium Limited"))
      (libsource (lib "Miscellaneous Devices") (part "Res3"))
    )
    (comp (ref "R35")
      (value "10K")
      (footprint "J1-0603")
      (description "Resistor")
      (fields (field (name "Comment") "Res3") (field (name "PUBLISHER") "Altium Limited"))
      (libsource (lib "Miscellaneous Devices") (part "Res3"))
    )
    (comp (ref "R36")
      (value "10K")
      (footprint "J1-0603")
      (description "Resistor")
      (fields (field (name "Comment") "Res3") (field (name "PUBLISHER") "Altium Limited"))
      (libsource (lib "Miscellaneous Devices") (part "Res3"))
    )
    (comp (ref "R37")
      (value "10K")
      (footprint "J1-0603")
      (description "Resistor")
      (fields (field (name "Comment") "Res3") (field (name "PUBLISHER") "Altium Limited"))
      (libsource (lib "Miscellaneous Devices") (part "Res3"))
    )
    (comp (ref "R38")
      (value "10K")
      (footprint "J1-0603")
      (description "Resistor")
      (fields (field (name "Comment") "Res3") (field (name "PUBLISHER") "Altium Limited"))
      (libsource (lib "Miscellaneous Devices") (part "Res3"))
    )
    (comp (ref "R39")
      (value "10K")
      (footprint "J1-0603")
      (description "Resistor")
      (fields (field (name "Comment") "Res3") (field (name "PUBLISHER") "Altium Limited"))
      (libsource (lib "Miscellaneous Devices") (part "Res3"))
    )
    (comp (ref "R40")
      (value "10K")
      (footprint "J1-0603")
      (description "Resistor")
      (fields (field (name "Comment") "Res3") (field (name "PUBLISHER") "Altium Limited"))
      (libsource (lib "Miscellaneous Devices") (part "Res3"))
    )
    (comp (ref "R41")
      (value "510R")
      (footprint "J1-0603")
      (description "Resistor")
      (fields (field (name "Comment") "Res3") (field (name "PUBLISHER") "Altium Limited"))
      (libsource (lib "Miscellaneous Devices") (part "Res3"))
    )
    (comp (ref "R42")
      (value "10K")
      (footprint "J1-0603")
      (description "Resistor")
      (fields (field (name "Comment") "Res3") (field (name "PUBLISHER") "Altium Limited"))
      (libsource (lib "Miscellaneous Devices") (part "Res3"))
    )
    (comp (ref "R43")
      (value "10K")
      (footprint "J1-0603")
      (description "Resistor")
      (fields (field (name "Comment") "Res3") (field (name "PUBLISHER") "Altium Limited"))
      (libsource (lib "Miscellaneous Devices") (part "Res3"))
    )
    (comp (ref "R44")
      (value "10K")
      (footprint "J1-0603")
      (description "Resistor")
      (fields (field (name "Comment") "Res3") (field (name "PUBLISHER") "Altium Limited"))
      (libsource (lib "Miscellaneous Devices") (part "Res3"))
    )
    (comp (ref "R45")
      (value "10K")
      (footprint "J1-0603")
      (description "Resistor")
      (fields (field (name "Comment") "Res3") (field (name "PUBLISHER") "Altium Limited"))
      (libsource (lib "Miscellaneous Devices") (part "Res3"))
    )
    (comp (ref "R46")
      (value "10K")
      (footprint "J1-0603")
      (description "Resistor")
      (fields (field (name "Comment") "Res3") (field (name "PUBLISHER") "Altium Limited"))
      (libsource (lib "Miscellaneous Devices") (part "Res3"))
    )
    (comp (ref "R47")
      (value "10K")
      (footprint "J1-0603")
      (description "Resistor")
      (fields (field (name "Comment") "Res3") (field (name "PUBLISHER") "Altium Limited"))
      (libsource (lib "Miscellaneous Devices") (part "Res3"))
    )
    (comp (ref "R48")
      (value "10K")
      (footprint "J1-0603")
      (description "Resistor")
      (fields (field (name "Comment") "Res3") (field (name "PUBLISHER") "Altium Limited"))
      (libsource (lib "Miscellaneous Devices") (part "Res3"))
    )
    (comp (ref "R49")
      (value "10K")
      (footprint "J1-0603")
      (description "Resistor")
      (fields (field (name "Comment") "Res3") (field (name "PUBLISHER") "Altium Limited"))
      (libsource (lib "Miscellaneous Devices") (part "Res3"))
    )
    (comp (ref "R51")
      (value "0R")
      (footprint "J1-0603")
      (description "Resistor")
      (fields (field (name "Comment") "Res3") (field (name "PUBLISHER") "Altium Limited"))
      (libsource (lib "Miscellaneous Devices") (part "Res3"))
    )
    (comp (ref "R53")
      (value "0R")
      (footprint "J1-0603")
      (description "Resistor")
      (fields (field (name "Comment") "Res3") (field (name "PUBLISHER") "Altium Limited"))
      (libsource (lib "Miscellaneous Devices") (part "Res3"))
    )
    (comp (ref "R54")
      (value "0R")
      (footprint "J1-0603")
      (description "Resistor")
      (fields (field (name "Comment") "Res3") (field (name "PUBLISHER") "Altium Limited"))
      (libsource (lib "Miscellaneous Devices") (part "Res3"))
    )
    (comp (ref "R55")
      (value "0R")
      (footprint "J1-0603")
      (description "Resistor")
      (fields (field (name "Comment") "Res3") (field (name "PUBLISHER") "Altium Limited"))
      (libsource (lib "Miscellaneous Devices") (part "Res3"))
    )
    (comp (ref "R56")
      (value "0R")
      (footprint "J1-0603")
      (description "Resistor")
      (fields (field (name "Comment") "Res3") (field (name "PUBLISHER") "Altium Limited"))
      (libsource (lib "Miscellaneous Devices") (part "Res3"))
    )
    (comp (ref "R57")
      (value "0R")
      (footprint "J1-0603")
      (description "Resistor")
      (fields (field (name "Comment") "Res3") (field (name "PUBLISHER") "Altium Limited"))
      (libsource (lib "Miscellaneous Devices") (part "Res3"))
    )
    (comp (ref "R58")
      (value "0R")
      (footprint "J1-0603")
      (description "Resistor")
      (fields (field (name "Comment") "Res3") (field (name "PUBLISHER") "Altium Limited"))
      (libsource (lib "Miscellaneous Devices") (part "Res3"))
    )
    (comp (ref "R59")
      (value "0R")
      (footprint "J1-0603")
      (description "Resistor")
      (fields (field (name "Comment") "Res3") (field (name "PUBLISHER") "Altium Limited"))
      (libsource (lib "Miscellaneous Devices") (part "Res3"))
    )
    (comp (ref "R84")
      (value "0R")
      (footprint "J1-0603")
      (description "Resistor")
      (fields (field (name "Comment") "Res3") (field (name "PUBLISHER") "Altium Limited"))
      (libsource (lib "Miscellaneous Devices") (part "Res3"))
    )
    (comp (ref "R88")
      (value "4.7K")
      (footprint "J1-0603")
      (description "Resistor")
      (fields (field (name "Comment") "Res3") (field (name "PUBLISHER") "Altium Limited"))
      (libsource (lib "Miscellaneous Devices") (part "Res3"))
    )
    (comp (ref "R89")
      (value "4.7K")
      (footprint "J1-0603")
      (description "Resistor")
      (fields (field (name "Comment") "Res3") (field (name "PUBLISHER") "Altium Limited"))
      (libsource (lib "Miscellaneous Devices") (part "Res3"))
    )
    (comp (ref "R90")
      (value "0R")
      (footprint "J1-0603")
      (description "Resistor")
      (fields (field (name "Comment") "Res3") (field (name "PUBLISHER") "Altium Limited"))
      (libsource (lib "Miscellaneous Devices") (part "Res3"))
    )
    (comp (ref "R92")
      (value "0R")
      (footprint "J1-0603")
      (description "Resistor")
      (fields (field (name "Comment") "Res3") (field (name "PUBLISHER") "Altium Limited"))
      (libsource (lib "Miscellaneous Devices") (part "Res3"))
    )
    (comp (ref "R93")
      (value "0R")
      (footprint "J1-0603")
      (description "Resistor")
      (fields (field (name "Comment") "Res3") (field (name "PUBLISHER") "Altium Limited"))
      (libsource (lib "Miscellaneous Devices") (part "Res3"))
    )
    (comp (ref "R94")
      (value "0R")
      (footprint "J1-0603")
      (description "Resistor")
      (fields (field (name "Comment") "Res3") (field (name "PUBLISHER") "Altium Limited"))
      (libsource (lib "Miscellaneous Devices") (part "Res3"))
    )
    (comp (ref "R103")
      (value "22R")
      (footprint "J1-0603")
      (description "Resistor")
      (fields (field (name "Comment") "Res3") (field (name "PUBLISHER") "Altium Limited"))
      (libsource (lib "Miscellaneous Devices") (part "Res3"))
    )
    (comp (ref "R104")
      (value "22R")
      (footprint "J1-0603")
      (description "Resistor")
      (fields (field (name "Comment") "Res3") (field (name "PUBLISHER") "Altium Limited"))
      (libsource (lib "Miscellaneous Devices") (part "Res3"))
    )
    (comp (ref "R105")
      (value "NC")
      (footprint "J1-0603")
      (description "Resistor")
      (fields (field (name "ALTIUM_VALUE") "0R") (field (name "PUBLISHER") "Altium Limited"))
      (libsource (lib "Miscellaneous Devices") (part "Res3"))
    )
    (comp (ref "R106")
      (value "15K")
      (footprint "J1-0603")
      (description "Resistor")
      (fields (field (name "Comment") "Res3") (field (name "PUBLISHER") "Altium Limited"))
      (libsource (lib "Miscellaneous Devices") (part "Res3"))
    )
    (comp (ref "R107")
      (value "15K")
      (footprint "J1-0603")
      (description "Resistor")
      (fields (field (name "Comment") "Res3") (field (name "PUBLISHER") "Altium Limited"))
      (libsource (lib "Miscellaneous Devices") (part "Res3"))
    )
    (comp (ref "R108")
      (value "0R")
      (footprint "J1-0603")
      (description "Resistor")
      (fields (field (name "Comment") "Res3") (field (name "PUBLISHER") "Altium Limited"))
      (libsource (lib "Miscellaneous Devices") (part "Res3"))
    )
    (comp (ref "R109")
      (value "0R")
      (footprint "J1-0603")
      (description "Resistor")
      (fields (field (name "Comment") "Res3") (field (name "PUBLISHER") "Altium Limited"))
      (libsource (lib "Miscellaneous Devices") (part "Res3"))
    )
    (comp (ref "R110")
      (value "0R")
      (footprint "J1-0603")
      (description "Resistor")
      (fields (field (name "Comment") "Res3") (field (name "PUBLISHER") "Altium Limited"))
      (libsource (lib "Miscellaneous Devices") (part "Res3"))
    )
    (comp (ref "R111")
      (value "100K")
      (footprint "J1-0603")
      (description "Resistor")
      (fields (field (name "Comment") "Res3") (field (name "PUBLISHER") "Altium Limited"))
      (libsource (lib "Miscellaneous Devices") (part "Res3"))
    )
    (comp (ref "R112")
      (value "100K")
      (footprint "J1-0603")
      (description "Resistor")
      (fields (field (name "Comment") "Res3") (field (name "PUBLISHER") "Altium Limited"))
      (libsource (lib "Miscellaneous Devices") (part "Res3"))
    )
    (comp (ref "R113")
      (value "47K")
      (footprint "J1-0603")
      (description "Resistor")
      (fields (field (name "Comment") "Res3") (field (name "PUBLISHER") "Altium Limited"))
      (libsource (lib "Miscellaneous Devices") (part "Res3"))
    )
    (comp (ref "R114")
      (value "22R")
      (footprint "J1-0603")
      (description "Resistor")
      (fields (field (name "Comment") "Res3") (field (name "PUBLISHER") "Altium Limited"))
      (libsource (lib "Miscellaneous Devices") (part "Res3"))
    )
    (comp (ref "R115")
      (value "22R")
      (footprint "J1-0603")
      (description "Resistor")
      (fields (field (name "Comment") "Res3") (field (name "PUBLISHER") "Altium Limited"))
      (libsource (lib "Miscellaneous Devices") (part "Res3"))
    )
    (comp (ref "R116")
      (value "100K")
      (footprint "J1-0603")
      (description "Resistor")
      (fields (field (name "Comment") "Res3") (field (name "PUBLISHER") "Altium Limited"))
      (libsource (lib "Miscellaneous Devices") (part "Res3"))
    )
    (comp (ref "R117")
      (value "15K")
      (footprint "J1-0603")
      (description "Resistor")
      (fields (field (name "Comment") "Res3") (field (name "PUBLISHER") "Altium Limited"))
      (libsource (lib "Miscellaneous Devices") (part "Res3"))
    )
    (comp (ref "R118")
      (value "15K")
      (footprint "J1-0603")
      (description "Resistor")
      (fields (field (name "Comment") "Res3") (field (name "PUBLISHER") "Altium Limited"))
      (libsource (lib "Miscellaneous Devices") (part "Res3"))
    )
    (comp (ref "R119")
      (value "2.7K/1%")
      (footprint "J1-0603")
      (description "Resistor")
      (fields (field (name "Comment") "Res3") (field (name "PUBLISHER") "Altium Limited"))
      (libsource (lib "Miscellaneous Devices") (part "Res3"))
    )
    (comp (ref "RA1/2")
      (value "22R")
      (footprint "SO-16_N")
      (description "Isolated Resistor Network")
      (fields (field (name "Comment") "Res Pack3") (field (name "PUBLISHER") "Altium Limited"))
      (libsource (lib "Miscellaneous Devices") (part "Res Pack3"))
    )
    (comp (ref "SW-1") (value "SW-normal") (libsource (lib "Schlib") (part "SW-normal")))
    (comp (ref "SW-2") (value "SW-normal") (libsource (lib "") (part "SW-normal_1")))
    (comp (ref "U1") (value "AMS1086CM-3.3") (libsource (lib "Schlib") (part "AMS1086CM-3.3")))
    (comp (ref "U2") (value "DM9000AE") (libsource (lib "Schlib") (part "DM9000AE")))
    (comp (ref "U3") (value "WM8960GEFL") (libsource (lib "Schlib") (part "WM8960GEFL")))
    (comp (ref "U4")
      (value "I2C_0")
      (footprint "HDR1X2")
      (description "Header, 2-Pin")
      (fields (field (name "PUBLISHER") "Altium Limited"))
      (libsource (lib "Miscellaneous Connectors") (part "Header 2"))
    )
    (comp (ref "U9") (value "USB HUB") (libsource (lib "Schlib") (part "USB HUB IC")))
    (comp (ref "Y1")
      (value "25MHz")
      (footprint "R38")
      (description "Crystal Oscillator")
      (fields (field (name "PUBLISHER") "Altium Limited"))
      (libsource (lib "Miscellaneous Devices") (part "XTAL"))
    )
    (comp (ref "Y2")
      (value "12MHz")
      (footprint "R38")
      (description "Crystal Oscillator")
      (fields (field (name "PUBLISHER") "Altium Limited"))
      (libsource (lib "Miscellaneous Devices") (part "XTAL"))
    )
  )
  (nets
    (net (code "1") (name "/3D+") (class "Default")
      (node (ref "J28") (pin "3") (pinfunction "D+_3") (pintype "passive"))
      (node (ref "R104") (pin "1") (pinfunction "1_1") (pintype "passive"))
      (node (ref "R106") (pin "2") (pinfunction "2_2") (pintype "passive"))
    )
    (net (code "2") (name "/3D-") (class "Default")
      (node (ref "J28") (pin "2") (pinfunction "D-_2") (pintype "passive"))
      (node (ref "R103") (pin "1") (pinfunction "1_1") (pintype "passive"))
      (node (ref "R107") (pin "2") (pinfunction "2_2") (pintype "passive"))
    )
    (net (code "3") (name "/4D+") (class "Default")
      (node (ref "J28") (pin "7") (pinfunction "D+_7") (pintype "passive"))
      (node (ref "R115") (pin "1") (pinfunction "1_1") (pintype "passive"))
      (node (ref "R117") (pin "2") (pinfunction "2_2") (pintype "passive"))
    )
    (net (code "4") (name "/4D-") (class "Default")
      (node (ref "J28") (pin "6") (pinfunction "D-_6") (pintype "passive"))
      (node (ref "R114") (pin "1") (pinfunction "1_1") (pintype "passive"))
      (node (ref "R118") (pin "2") (pinfunction "2_2") (pintype "passive"))
    )
    (net (code "5") (name "/ADCIN0") (class "Default")
      (node (ref "J1") (pin "39") (pinfunction "39_39") (pintype "passive"))
      (node (ref "J5") (pin "23") (pinfunction "23_23") (pintype "passive"))
    )
    (net (code "6") (name "/ADCIN1") (class "Default")
      (node (ref "J1") (pin "40") (pinfunction "40_40") (pintype "passive"))
      (node (ref "J5") (pin "24") (pinfunction "24_24") (pintype "passive"))
    )
    (net (code "7") (name "/ADDR0") (class "Default")
      (node (ref "J3") (pin "35") (pinfunction "35_35") (pintype "passive"))
    )
    (net (code "8") (name "/ADDR1") (class "Default")
      (node (ref "J3") (pin "36") (pinfunction "36_36") (pintype "passive"))
    )
    (net (code "9") (name "/ADDR2") (class "Default")
      (node (ref "J3") (pin "37") (pinfunction "37_37") (pintype "passive"))
      (node (ref "U2") (pin "32") (pinfunction "CMD_32") (pintype "passive"))
    )
    (net (code "10") (name "/ADDR15") (class "Default")
      (node (ref "J3") (pin "38") (pinfunction "38_38") (pintype "passive"))
    )
    (net (code "11") (name "/CAM_CLKOUT") (class "Default")
      (node (ref "J12") (pin "8") (pinfunction "8_8") (pintype "passive"))
      (node (ref "J4") (pin "8") (pinfunction "8_8") (pintype "passive"))
    )
    (net (code "12") (name "/CAM_D0") (class "Default")
      (node (ref "J12") (pin "16") (pinfunction "16_16") (pintype "passive"))
      (node (ref "J4") (pin "16") (pinfunction "16_16") (pintype "passive"))
    )
    (net (code "13") (name "/CAM_D1") (class "Default")
      (node (ref "J4") (pin "15") (pinfunction "15_15") (pintype "passive"))
    )
    (net (code "14") (name "/CAM_D2") (class "Default")
      (node (ref "J12") (pin "14") (pinfunction "14_14") (pintype "passive"))
      (node (ref "J4") (pin "14") (pinfunction "14_14") (pintype "passive"))
    )
    (net (code "15") (name "/CAM_D3") (class "Default")
      (node (ref "J12") (pin "13") (pinfunction "13_13") (pintype "passive"))
      (node (ref "J4") (pin "13") (pinfunction "13_13") (pintype "passive"))
    )
    (net (code "16") (name "/CAM_D4") (class "Default")
      (node (ref "J12") (pin "12") (pinfunction "12_12") (pintype "passive"))
      (node (ref "J4") (pin "12") (pinfunction "12_12") (pintype "passive"))
    )
    (net (code "17") (name "/CAM_D5") (class "Default")
      (node (ref "J12") (pin "11") (pinfunction "11_11") (pintype "passive"))
      (node (ref "J4") (pin "11") (pinfunction "11_11") (pintype "passive"))
    )
    (net (code "18") (name "/CAM_D6") (class "Default")
      (node (ref "J12") (pin "10") (pinfunction "10_10") (pintype "passive"))
      (node (ref "J4") (pin "10") (pinfunction "10_10") (pintype "passive"))
    )
    (net (code "19") (name "/CAM_D7") (class "Default")
      (node (ref "J12") (pin "9") (pinfunction "9_9") (pintype "passive"))
      (node (ref "J4") (pin "9") (pinfunction "9_9") (pintype "passive"))
    )
    (net (code "20") (name "/CAM_HREF") (class "Default")
      (node (ref "J12") (pin "6") (pinfunction "6_6") (pintype "passive"))
      (node (ref "J4") (pin "6") (pinfunction "6_6") (pintype "passive"))
    )
    (net (code "21") (name "/CAM_PCKL") (class "Default")
      (node (ref "J12") (pin "5") (pinfunction "5_5") (pintype "passive"))
      (node (ref "J4") (pin "5") (pinfunction "5_5") (pintype "passive"))
    )
    (net (code "22") (name "/CAM_VSYNC") (class "Default")
      (node (ref "J12") (pin "7") (pinfunction "7_7") (pintype "passive"))
      (node (ref "J4") (pin "7") (pinfunction "7_7") (pintype "passive"))
    )
    (net (code "23") (name "/CSn1") (class "Default")
      (node (ref "J3") (pin "39") (pinfunction "39_39") (pintype "passive"))
      (node (ref "U2") (pin "37") (pinfunction "CS#_37") (pintype "passive"))
    )
    (net (code "24") (name "/DAC_OUT0") (class "Default")
      (node (ref "J1") (pin "51") (pinfunction "51_51") (pintype "passive"))
    )
    (net (code "25") (name "/DATA0") (class "Default")
      (node (ref "J3") (pin "45") (pinfunction "45_45") (pintype "passive"))
      (node (ref "U2") (pin "18") (pinfunction "SD0_18") (pintype "passive"))
    )
    (net (code "26") (name "/DATA1") (class "Default")
      (node (ref "J3") (pin "46") (pinfunction "46_46") (pintype "passive"))
      (node (ref "U2") (pin "17") (pinfunction "SD1_17") (pintype "passive"))
    )
    (net (code "27") (name "/DATA2") (class "Default")
      (node (ref "J3") (pin "47") (pinfunction "47_47") (pintype "passive"))
      (node (ref "U2") (pin "16") (pinfunction "SD2_16") (pintype "passive"))
    )
    (net (code "28") (name "/DATA3") (class "Default")
      (node (ref "J3") (pin "48") (pinfunction "48_48") (pintype "passive"))
      (node (ref "U2") (pin "14") (pinfunction "SD3_14") (pintype "passive"))
    )
    (net (code "29") (name "/DATA4") (class "Default")
      (node (ref "J3") (pin "49") (pinfunction "49_49") (pintype "passive"))
      (node (ref "U2") (pin "13") (pinfunction "SD4_13") (pintype "passive"))
    )
    (net (code "30") (name "/DATA5") (class "Default")
      (node (ref "J3") (pin "50") (pinfunction "50_50") (pintype "passive"))
      (node (ref "U2") (pin "12") (pinfunction "SD5_12") (pintype "passive"))
    )
    (net (code "31") (name "/DATA6") (class "Default")
      (node (ref "J3") (pin "51") (pinfunction "51_51") (pintype "passive"))
      (node (ref "U2") (pin "11") (pinfunction "SD6_11") (pintype "passive"))
    )
    (net (code "32") (name "/DATA7") (class "Default")
      (node (ref "J3") (pin "52") (pinfunction "52_52") (pintype "passive"))
      (node (ref "U2") (pin "10") (pinfunction "SD7_10") (pintype "passive"))
    )
    (net (code "33") (name "/DATA8") (class "Default")
      (node (ref "J3") (pin "53") (pinfunction "53_53") (pintype "passive"))
      (node (ref "U2") (pin "31") (pinfunction "SD8_31") (pintype "passive"))
    )
    (net (code "34") (name "/DATA9") (class "Default")
      (node (ref "J3") (pin "54") (pinfunction "54_54") (pintype "passive"))
      (node (ref "U2") (pin "29") (pinfunction "SD9_29") (pintype "passive"))
    )
    (net (code "35") (name "/DATA10") (class "Default")
      (node (ref "J3") (pin "55") (pinfunction "55_55") (pintype "passive"))
      (node (ref "U2") (pin "28") (pinfunction "SD10_28") (pintype "passive"))
    )
    (net (code "36") (name "/DATA11") (class "Default")
      (node (ref "J3") (pin "56") (pinfunction "56_56") (pintype "passive"))
      (node (ref "U2") (pin "27") (pinfunction "SD11_27") (pintype "passive"))
    )
    (net (code "37") (name "/DATA12") (class "Default")
      (node (ref "J3") (pin "57") (pinfunction "57_57") (pintype "passive"))
      (node (ref "U2") (pin "26") (pinfunction "SD12_26") (pintype "passive"))
    )
    (net (code "38") (name "/DATA13") (class "Default")
      (node (ref "J3") (pin "58") (pinfunction "58_58") (pintype "passive"))
      (node (ref "U2") (pin "25") (pinfunction "SD13_25") (pintype "passive"))
    )
    (net (code "39") (name "/DATA14") (class "Default")
      (node (ref "J3") (pin "59") (pinfunction "59_59") (pintype "passive"))
      (node (ref "U2") (pin "24") (pinfunction "SD14_24") (pintype "passive"))
    )
    (net (code "40") (name "/DATA15") (class "Default")
      (node (ref "J3") (pin "60") (pinfunction "60_60") (pintype "passive"))
      (node (ref "U2") (pin "22") (pinfunction "SD15_22") (pintype "passive"))
    )
    (net (code "41") (name "/DM9000_LAN_LED") (class "Default")
      (node (ref "J9") (pin "11") (pinfunction "LEDY-_11") (pintype "passive"))
      (node (ref "U2") (pin "39") (pinfunction "LED1_39") (pintype "passive"))
    )
    (net (code "42") (name "/DM9000_LINK_LED") (class "Default")
      (node (ref "J9") (pin "10") (pinfunction "LEDG-_10") (pintype "passive"))
      (node (ref "U2") (pin "38") (pinfunction "LED2_38") (pintype "passive"))
    )
    (net (code "43") (name "/DM9000_RX+") (class "Default")
      (node (ref "J9") (pin "3") (pinfunction "RX-_3") (pintype "passive"))
      (node (ref "R8") (pin "2") (pinfunction "2_2") (pintype "passive"))
      (node (ref "U2") (pin "3") (pinfunction "RX+_3") (pintype "passive"))
    )
    (net (code "44") (name "/DM9000_RX-") (class "Default")
      (node (ref "J9") (pin "6") (pinfunction "RX-_6") (pintype "passive"))
      (node (ref "R9") (pin "2") (pinfunction "2_2") (pintype "passive"))
      (node (ref "U2") (pin "4") (pinfunction "RX-_4") (pintype "passive"))
    )
    (net (code "45") (name "/DM9000_TX+") (class "Default")
      (node (ref "J9") (pin "1") (pinfunction "TD+_1") (pintype "passive"))
      (node (ref "R6") (pin "2") (pinfunction "2_2") (pintype "passive"))
      (node (ref "U2") (pin "7") (pinfunction "TX+_7") (pintype "passive"))
    )
    (net (code "46") (name "/DM9000_TX-") (class "Default")
      (node (ref "J9") (pin "2") (pinfunction "TD-_2") (pintype "passive"))
      (node (ref "R7") (pin "2") (pinfunction "2_2") (pintype "passive"))
      (node (ref "U2") (pin "8") (pinfunction "TX-_8") (pintype "passive"))
    )
    (net (code "47") (name "/EINT0") (class "Default")
      (node (ref "J3") (pin "64") (pinfunction "64_64") (pintype "passive"))
      (node (ref "J5") (pin "15") (pinfunction "15_15") (pintype "passive"))
    )
    (net (code "48") (name "/EINT1") (class "Default")
      (node (ref "J3") (pin "66") (pinfunction "66_66") (pintype "passive"))
      (node (ref "J5") (pin "16") (pinfunction "16_16") (pintype "passive"))
    )
    (net (code "49") (name "/EINT3") (class "Default")
      (node (ref "J3") (pin "61") (pinfunction "61_61") (pintype "passive"))
      (node (ref "J5") (pin "17") (pinfunction "17_17") (pintype "passive"))
    )
    (net (code "50") (name "/EINT4") (class "Default")
      (node (ref "J3") (pin "63") (pinfunction "63_63") (pintype "passive"))
      (node (ref "J5") (pin "19") (pinfunction "19_19") (pintype "passive"))
    )
    (net (code "51") (name "/EINT5") (class "Default")
      (node (ref "J3") (pin "65") (pinfunction "65_65") (pintype "passive"))
      (node (ref "J5") (pin "18") (pinfunction "18_18") (pintype "passive"))
    )
    (net (code "52") (name "/EINT6") (class "Default")
      (node (ref "J3") (pin "24") (pinfunction "24_24") (pintype "passive"))
      (node (ref "RA1/2") (pin "7") (pinfunction "7_7") (pintype "passive"))
    )
    (net (code "53") (name "/EINT7") (class "Default")
      (node (ref "J3") (pin "40") (pinfunction "40_40") (pintype "passive"))
      (node (ref "U2") (pin "34") (pinfunction "INT_34") (pintype "passive"))
    )
    (net (code "54") (name "/EINT8") (class "Default")
      (node (ref "J1") (pin "30") (pinfunction "30_30") (pintype "passive"))
      (node (ref "J14") (pin "18") (pinfunction "18_18") (pintype "passive"))
    )
    (net (code "55") (name "/EINT9") (class "Default")
      (node (ref "J3") (pin "34") (pinfunction "34_34") (pintype "passive"))
      (node (ref "J5") (pin "20") (pinfunction "20_20") (pintype "passive"))
    )
    (net (code "56") (name "/EINT10") (class "Default")
      (node (ref "J1") (pin "22") (pinfunction "22_22") (pintype "passive"))
      (node (ref "J24_B") (pin "11") (pinfunction "11_11") (pintype "passive"))
    )
    (net (code "57") (name "/EINT11") (class "Default")
      (node (ref "J1") (pin "46") (pinfunction "46_46") (pintype "passive"))
    )
    (net (code "58") (name "/EINT14") (class "Default")
      (node (ref "J4") (pin "24") (pinfunction "24_24") (pintype "passive"))
      (node (ref "R92") (pin "1") (pinfunction "1_1") (pintype "passive"))
    )
    (net (code "59") (name "/EINT15") (class "Default")
      (node (ref "J4") (pin "22") (pinfunction "22_22") (pintype "passive"))
      (node (ref "R94") (pin "1") (pinfunction "1_1") (pintype "passive"))
    )
    (net (code "60") (name "/GPJ2_6") (class "Default")
      (node (ref "J12") (pin "3") (pinfunction "3_3") (pintype "passive"))
      (node (ref "J4") (pin "3") (pinfunction "3_3") (pintype "passive"))
    )
    (net (code "61") (name "/GPJ3_1") (class "Default")
      (node (ref "J12") (pin "4") (pinfunction "4_4") (pintype "passive"))
      (node (ref "J4") (pin "4") (pinfunction "4_4") (pintype "passive"))
    )
    (net (code "62") (name "/GPJ3_6") (class "Default")
      (node (ref "J1") (pin "42") (pinfunction "42_42") (pintype "passive"))
    )
    (net (code "63") (name "/GPJ3_7") (class "Default")
      (node (ref "J1") (pin "41") (pinfunction "41_41") (pintype "passive"))
      (node (ref "J16") (pin "11") (pinfunction "11_11") (pintype "passive"))
      (node (ref "R27") (pin "1") (pinfunction "1_1") (pintype "passive"))
    )
    (net (code "64") (name "/HOST_DN") (class "Default")
      (node (ref "J1") (pin "32") (pinfunction "32_32") (pintype "passive"))
      (node (ref "R105") (pin "2") (pinfunction "2_2") (pintype "passive"))
      (node (ref "U9") (pin "15") (pinfunction "DMU_15") (pintype "passive"))
    )
    (net (code "65") (name "/HOST_DP") (class "Default")
      (node (ref "J1") (pin "34") (pinfunction "34_34") (pintype "passive"))
      (node (ref "R108") (pin "2") (pinfunction "2_2") (pintype "passive"))
      (node (ref "U9") (pin "16") (pinfunction "DPU_16") (pintype "passive"))
    )
    (net (code "66") (name "/HSYNC") (class "Default")
      (node (ref "J1") (pin "24") (pinfunction "24_24") (pintype "passive"))
      (node (ref "J24_B") (pin "15") (pinfunction "15_15") (pintype "passive"))
    )
    (net (code "67") (name "/I2CSSDI0") (class "Default")
      (node (ref "J3") (pin "33") (pinfunction "33_33") (pintype "passive"))
    )
    (net (code "68") (name "/I2C_SCL0") (class "Default")
      (node (ref "J12") (pin "2") (pinfunction "2_2") (pintype "passive"))
      (node (ref "J14") (pin "5") (pinfunction "5_5") (pintype "passive"))
      (node (ref "J16") (pin "5") (pinfunction "5_5") (pintype "passive"))
      (node (ref "J3") (pin "19") (pinfunction "19_19") (pintype "passive"))
      (node (ref "J4") (pin "2") (pinfunction "2_2") (pintype "passive"))
      (node (ref "U3") (pin "17") (pinfunction "SCLK_17") (pintype "passive"))
      (node (ref "U4") (pin "1") (pinfunction "1_1") (pintype "passive"))
    )
    (net (code "69") (name "/I2C_SCL2") (class "Default")
      (node (ref "J4") (pin "23") (pinfunction "23_23") (pintype "passive"))
      (node (ref "R89") (pin "2") (pinfunction "2_2") (pintype "passive"))
      (node (ref "R90") (pin "1") (pinfunction "1_1") (pintype "passive"))
    )
    (net (code "70") (name "/I2C_SDA0") (class "Default")
      (node (ref "J12") (pin "1") (pinfunction "1_1") (pintype "passive"))
      (node (ref "J14") (pin "6") (pinfunction "6_6") (pintype "passive"))
      (node (ref "J3") (pin "20") (pinfunction "20_20") (pintype "passive"))
      (node (ref "J4") (pin "1") (pinfunction "1_1") (pintype "passive"))
      (node (ref "U3") (pin "18") (pinfunction "SDIN_18") (pintype "passive"))
      (node (ref "U4") (pin "2") (pinfunction "2_2") (pintype "passive"))
    )
    (net (code "71") (name "/I2C_SDA2") (class "Default")
      (node (ref "J4") (pin "21") (pinfunction "21_21") (pintype "passive"))
    )
    (net (code "72") (name "/I2C_SDA3") (class "Default")
      (node (ref "R88") (pin "2") (pinfunction "2_2") (pintype "passive"))
      (node (ref "R93") (pin "1") (pinfunction "1_1") (pintype "passive"))
    )
    (net (code "73") (name "/I2SCDCLK0") (class "Default")
      (node (ref "J3") (pin "30") (pinfunction "30_30") (pintype "passive"))
      (node (ref "R11") (pin "2") (pinfunction "2_2") (pintype "passive"))
      (node (ref "U3") (pin "11") (pinfunction "MCLK_11") (pintype "passive"))
      (node (ref "U3") (pin "14") (pinfunction "DACDAT_14") (pintype "passive"))
    )
    (net (code "74") (name "/I2SLRCK0") (class "Default")
      (node (ref "J3") (pin "31") (pinfunction "31_31") (pintype "passive"))
      (node (ref "R13") (pin "2") (pinfunction "2_2") (pintype "passive"))
      (node (ref "U3") (pin "13") (pinfunction "DACLRC_13") (pintype "passive"))
    )
    (net (code "75") (name "/I2SSCLK0") (class "Default")
      (node (ref "J3") (pin "29") (pinfunction "29_29") (pintype "passive"))
      (node (ref "R12") (pin "2") (pinfunction "2_2") (pintype "passive"))
      (node (ref "U3") (pin "12") (pinfunction "BCLK_12") (pintype "passive"))
    )
    (net (code "76") (name "/I2SSDI0") (class "Default")
      (node (ref "U3") (pin "16") (pinfunction "ADCDAT_16") (pintype "passive"))
    )
    (net (code "77") (name "/I2SSDO0_0") (class "Default")
      (node (ref "J3") (pin "32") (pinfunction "32_32") (pintype "passive"))
    )
    (net (code "78") (name "/KP_COL0") (class "Default")
      (node (ref "J1") (pin "53") (pinfunction "53_53") (pintype "passive"))
      (node (ref "J5") (pin "14") (pinfunction "14_14") (pintype "passive"))
      (node (ref "R51") (pin "1") (pinfunction "1_1") (pintype "passive"))
    )
    (net (code "79") (name "/KP_COL1") (class "Default")
      (node (ref "J1") (pin "54") (pinfunction "54_54") (pintype "passive"))
      (node (ref "J5") (pin "12") (pinfunction "12_12") (pintype "passive"))
      (node (ref "R53") (pin "1") (pinfunction "1_1") (pintype "passive"))
    )
    (net (code "80") (name "/KP_COL2") (class "Default")
      (node (ref "J1") (pin "55") (pinfunction "55_55") (pintype "passive"))
      (node (ref "J5") (pin "10") (pinfunction "10_10") (pintype "passive"))
      (node (ref "R54") (pin "1") (pinfunction "1_1") (pintype "passive"))
    )
    (net (code "81") (name "/KP_COL3") (class "Default")
      (node (ref "J1") (pin "56") (pinfunction "56_56") (pintype "passive"))
      (node (ref "J5") (pin "8") (pinfunction "8_8") (pintype "passive"))
      (node (ref "R55") (pin "1") (pinfunction "1_1") (pintype "passive"))
    )
    (net (code "82") (name "/KP_ROW0") (class "Default")
      (node (ref "J1") (pin "57") (pinfunction "57_57") (pintype "passive"))
      (node (ref "J5") (pin "13") (pinfunction "13_13") (pintype "passive"))
      (node (ref "R56") (pin "1") (pinfunction "1_1") (pintype "passive"))
    )
    (net (code "83") (name "/KP_ROW1") (class "Default")
      (node (ref "J1") (pin "58") (pinfunction "58_58") (pintype "passive"))
      (node (ref "J5") (pin "11") (pinfunction "11_11") (pintype "passive"))
      (node (ref "R57") (pin "1") (pinfunction "1_1") (pintype "passive"))
    )
    (net (code "84") (name "/KP_ROW2") (class "Default")
      (node (ref "J1") (pin "59") (pinfunction "59_59") (pintype "passive"))
      (node (ref "J5") (pin "9") (pinfunction "9_9") (pintype "passive"))
      (node (ref "R58") (pin "1") (pinfunction "1_1") (pintype "passive"))
    )
    (net (code "85") (name "/KP_ROW3") (class "Default")
      (node (ref "J1") (pin "60") (pinfunction "60_60") (pintype "passive"))
      (node (ref "J5") (pin "7") (pinfunction "7_7") (pintype "passive"))
      (node (ref "R59") (pin "1") (pinfunction "1_1") (pintype "passive"))
    )
    (net (code "86") (name "/MMC0_CDn") (class "Default")
      (node (ref "J3") (pin "23") (pinfunction "23_23") (pintype "passive"))
      (node (ref "RA1/2") (pin "8") (pinfunction "8_8") (pintype "passive"))
    )
    (net (code "87") (name "/MMC0_CLK") (class "Default")
      (node (ref "J3") (pin "21") (pinfunction "21_21") (pintype "passive"))
      (node (ref "RA1/2") (pin "4") (pinfunction "4_4") (pintype "passive"))
    )
    (net (code "88") (name "/MMC0_CMD") (class "Default")
      (node (ref "J3") (pin "22") (pinfunction "22_22") (pintype "passive"))
      (node (ref "RA1/2") (pin "3") (pinfunction "3_3") (pintype "passive"))
    )
    (net (code "89") (name "/MMC0_D0") (class "Default")
      (node (ref "J3") (pin "25") (pinfunction "25_25") (pintype "passive"))
      (node (ref "RA1/2") (pin "5") (pinfunction "5_5") (pintype "passive"))
    )
    (net (code "90") (name "/MMC0_D1") (class "Default")
      (node (ref "J3") (pin "26") (pinfunction "26_26") (pintype "passive"))
      (node (ref "RA1/2") (pin "6") (pinfunction "6_6") (pintype "passive"))
    )
    (net (code "91") (name "/MMC0_D2") (class "Default")
      (node (ref "J3") (pin "27") (pinfunction "27_27") (pintype "passive"))
      (node (ref "RA1/2") (pin "1") (pinfunction "1_1") (pintype "passive"))
    )
    (net (code "92") (name "/MMC0_D3") (class "Default")
      (node (ref "J3") (pin "28") (pinfunction "28_28") (pintype "passive"))
      (node (ref "RA1/2") (pin "2") (pinfunction "2_2") (pintype "passive"))
    )
    (net (code "93") (name "/MMC2_CDn") (class "Default")
      (node (ref "J1") (pin "45") (pinfunction "45_45") (pintype "passive"))
      (node (ref "J16") (pin "15") (pinfunction "15_15") (pintype "passive"))
      (node (ref "R23") (pin "1") (pinfunction "1_1") (pintype "passive"))
    )
    (net (code "94") (name "/MMC2_CLK") (class "Default")
      (node (ref "J1") (pin "43") (pinfunction "43_43") (pintype "passive"))
      (node (ref "J16") (pin "13") (pinfunction "13_13") (pintype "passive"))
      (node (ref "R22") (pin "1") (pinfunction "1_1") (pintype "passive"))
    )
    (net (code "95") (name "/MMC2_CMD") (class "Default")
      (node (ref "J1") (pin "44") (pinfunction "44_44") (pintype "passive"))
    )
    (net (code "96") (name "/MMC2_D0") (class "Default")
      (node (ref "J1") (pin "47") (pinfunction "47_47") (pintype "passive"))
      (node (ref "J16") (pin "17") (pinfunction "17_17") (pintype "passive"))
      (node (ref "R24") (pin "1") (pinfunction "1_1") (pintype "passive"))
    )
    (net (code "97") (name "/MMC2_D1") (class "Default")
      (node (ref "J1") (pin "48") (pinfunction "48_48") (pintype "passive"))
    )
    (net (code "98") (name "/MMC2_D2") (class "Default")
      (node (ref "J1") (pin "49") (pinfunction "49_49") (pintype "passive"))
      (node (ref "J16") (pin "19") (pinfunction "19_19") (pintype "passive"))
      (node (ref "R25") (pin "1") (pinfunction "1_1") (pintype "passive"))
    )
    (net (code "99") (name "/MMC2_D3") (class "Default")
      (node (ref "J1") (pin "50") (pinfunction "50_50") (pintype "passive"))
    )
    (net (code "100") (name "/M_nRESET") (class "Default")
      (node (ref "J3") (pin "3") (pinfunction "3_3") (pintype "passive"))
      (node (ref "K1") (pin "2") (pinfunction "2_2") (pintype "passive"))
    )
    (net (code "101") (name "/NET_AVDD25") (class "Default")
      (node (ref "C10") (pin "1") (pinfunction "1_1") (pintype "passive"))
      (node (ref "C8") (pin "2") (pinfunction "2_2") (pintype "passive"))
      (node (ref "C9") (pin "2") (pinfunction "2_2") (pintype "passive"))
      (node (ref "J9") (pin "4") (pinfunction "CT2_4") (pintype "passive"))
      (node (ref "J9") (pin "5") (pinfunction "CT1_5") (pintype "passive"))
      (node (ref "U2") (pin "2") (pinfunction "AVDD25_1_2") (pintype "passive"))
      (node (ref "U2") (pin "9") (pinfunction "AVDD25_0_9") (pintype "passive"))
    )
    (net (code "102") (name "/OEn") (class "Default")
      (node (ref "J3") (pin "44") (pinfunction "44_44") (pintype "passive"))
      (node (ref "U2") (pin "35") (pinfunction "IOR#_35") (pintype "passive"))
    )
    (net (code "103") (name "/OM1") (class "Default")
      (node (ref "J3") (pin "1") (pinfunction "1_1") (pintype "passive"))
      (node (ref "R1") (pin "1") (pinfunction "1_1") (pintype "passive"))
    )
    (net (code "104") (name "/OTG_DM") (class "Default")
      (node (ref "C46") (pin "1") (pinfunction "1_1") (pintype "passive"))
      (node (ref "J1") (pin "31") (pinfunction "31_31") (pintype "passive"))
      (node (ref "J13") (pin "2") (pinfunction "D-_2") (pintype "passive"))
    )
    (net (code "105") (name "/OTG_DP") (class "Default")
      (node (ref "J1") (pin "33") (pinfunction "33_33") (pintype "passive"))
      (node (ref "J13") (pin "3") (pinfunction "D+_3") (pintype "passive"))
    )
    (net (code "106") (name "/OTG_DRVVBUS") (class "Default")
      (node (ref "J1") (pin "28") (pinfunction "28_28") (pintype "passive"))
    )
    (net (code "107") (name "/OTG_ID") (class "Default")
      (node (ref "J1") (pin "29") (pinfunction "29_29") (pintype "passive"))
      (node (ref "J13") (pin "4") (pinfunction "ID_4") (pintype "passive"))
    )
    (net (code "108") (name "/PWMTOUT0") (class "Default")
      (node (ref "J1") (pin "52") (pinfunction "52_52") (pintype "passive"))
      (node (ref "R20") (pin "2") (pinfunction "2_2") (pintype "passive"))
    )
    (net (code "109") (name "/PWMTOUT1") (class "Default")
      (node (ref "J1") (pin "26") (pinfunction "26_26") (pintype "passive"))
    )
    (net (code "110") (name "/RXD0") (class "Default")
      (node (ref "J19") (pin "2") (pinfunction "2_2") (pintype "passive"))
      (node (ref "J3") (pin "8") (pinfunction "8_8") (pintype "passive"))
    )
    (net (code "111") (name "/RXD1") (class "Default")
      (node (ref "J14") (pin "8") (pinfunction "8_8") (pintype "passive"))
      (node (ref "J3") (pin "10") (pinfunction "10_10") (pintype "passive"))
    )
    (net (code "112") (name "/RXD2") (class "Default")
      (node (ref "J14") (pin "12") (pinfunction "12_12") (pintype "passive"))
      (node (ref "J3") (pin "12") (pinfunction "12_12") (pintype "passive"))
    )
    (net (code "113") (name "/RXD3") (class "Default")
      (node (ref "J3") (pin "14") (pinfunction "14_14") (pintype "passive"))
    )
    (net (code "114") (name "/SPI1_CLK") (class "Default")
      (node (ref "J14") (pin "16") (pinfunction "16_16") (pintype "passive"))
      (node (ref "J16") (pin "9") (pinfunction "9_9") (pintype "passive"))
      (node (ref "J3") (pin "17") (pinfunction "17_17") (pintype "passive"))
    )
    (net (code "115") (name "/SPI1_CSn") (class "Default")
      (node (ref "J14") (pin "15") (pinfunction "15_15") (pintype "passive"))
      (node (ref "J3") (pin "18") (pinfunction "18_18") (pintype "passive"))
    )
    (net (code "116") (name "/SPI1_MISO") (class "Default")
      (node (ref "J14") (pin "14") (pinfunction "14_14") (pintype "passive"))
      (node (ref "J3") (pin "15") (pinfunction "15_15") (pintype "passive"))
    )
    (net (code "117") (name "/SPI1_MOSI") (class "Default")
      (node (ref "J14") (pin "13") (pinfunction "13_13") (pintype "passive"))
      (node (ref "J16") (pin "7") (pinfunction "7_7") (pintype "passive"))
      (node (ref "J3") (pin "16") (pinfunction "16_16") (pintype "passive"))
    )
    (net (code "118") (name "/SPK_LN") (class "Default")
      (node (ref "C34") (pin "1") (pinfunction "1_1") (pintype "passive"))
      (node (ref "J10") (pin "3") (pinfunction "3_3") (pintype "passive"))
      (node (ref "U3") (pin "23") (pinfunction "SPK_LN_23") (pintype "passive"))
    )
    (net (code "119") (name "/SPK_LP") (class "Default")
      (node (ref "C33") (pin "1") (pinfunction "1_1") (pintype "passive"))
      (node (ref "J10") (pin "4") (pinfunction "4_4") (pintype "passive"))
      (node (ref "U3") (pin "25") (pinfunction "SPK_LP_25") (pintype "passive"))
    )
    (net (code "120") (name "/SPK_RN") (class "Default")
      (node (ref "C36") (pin "1") (pinfunction "1_1") (pintype "passive"))
      (node (ref "J10") (pin "1") (pinfunction "1_1") (pintype "passive"))
      (node (ref "U3") (pin "19") (pinfunction "SPK_RN_19") (pintype "passive"))
    )
    (net (code "121") (name "/SPK_RP") (class "Default")
      (node (ref "C35") (pin "1") (pinfunction "1_1") (pintype "passive"))
      (node (ref "J10") (pin "2") (pinfunction "2_2") (pintype "passive"))
      (node (ref "U3") (pin "22") (pinfunction "SPK_RP_22") (pintype "passive"))
    )
    (net (code "122") (name "/TCK") (class "Default")
      (node (ref "J1") (pin "66") (pinfunction "66_66") (pintype "passive"))
    )
    (net (code "123") (name "/TDI") (class "Default")
      (node (ref "J1") (pin "61") (pinfunction "61_61") (pintype "passive"))
    )
    (net (code "124") (name "/TDO") (class "Default")
      (node (ref "J1") (pin "63") (pinfunction "63_63") (pintype "passive"))
    )
    (net (code "125") (name "/TMS") (class "Default")
      (node (ref "J1") (pin "64") (pinfunction "64_64") (pintype "passive"))
    )
    (net (code "126") (name "/TRSTn") (class "Default")
      (node (ref "J1") (pin "62") (pinfunction "62_62") (pintype "passive"))
    )
    (net (code "127") (name "/TXD0") (class "Default")
      (node (ref "J19") (pin "1") (pinfunction "1_1") (pintype "passive"))
      (node (ref "J3") (pin "7") (pinfunction "7_7") (pintype "passive"))
    )
    (net (code "128") (name "/TXD1") (class "Default")
      (node (ref "J14") (pin "7") (pinfunction "7_7") (pintype "passive"))
      (node (ref "J3") (pin "9") (pinfunction "9_9") (pintype "passive"))
    )
    (net (code "129") (name "/TXD2") (class "Default")
      (node (ref "J14") (pin "11") (pinfunction "11_11") (pintype "passive"))
      (node (ref "J3") (pin "11") (pinfunction "11_11") (pintype "passive"))
    )
    (net (code "130") (name "/TXD3") (class "Default")
      (node (ref "J3") (pin "13") (pinfunction "13_13") (pintype "passive"))
    )
    (net (code "131") (name "/VBUS") (class "Default")
      (node (ref "C45") (pin "1") (pinfunction "1_1") (pintype "passive"))
      (node (ref "J1") (pin "27") (pinfunction "27_27") (pintype "passive"))
      (node (ref "J13") (pin "1") (pinfunction "VBUS_1") (pintype "passive"))
    )
    (net (code "132") (name "/VCLK") (class "Default")
      (node (ref "J1") (pin "25") (pinfunction "25_25") (pintype "passive"))
      (node (ref "J24_B") (pin "16") (pinfunction "16_16") (pintype "passive"))
    )
    (net (code "133") (name "/VD0") (class "Default")
      (node (ref "J24_A") (pin "3") (pinfunction "3_3") (pintype "passive"))
      (node (ref "J4") (pin "25") (pinfunction "25_25") (pintype "passive"))
    )
    (net (code "134") (name "/VD1") (class "Default")
      (node (ref "J24_A") (pin "4") (pinfunction "4_4") (pintype "passive"))
      (node (ref "J4") (pin "26") (pinfunction "26_26") (pintype "passive"))
    )
    (net (code "135") (name "/VD2") (class "Default")
      (node (ref "J1") (pin "20") (pinfunction "20_20") (pintype "passive"))
      (node (ref "J24_A") (pin "5") (pinfunction "5_5") (pintype "passive"))
    )
    (net (code "136") (name "/VD3") (class "Default")
      (node (ref "J1") (pin "19") (pinfunction "19_19") (pintype "passive"))
      (node (ref "J24_A") (pin "6") (pinfunction "6_6") (pintype "passive"))
    )
    (net (code "137") (name "/VD4") (class "Default")
      (node (ref "J1") (pin "18") (pinfunction "18_18") (pintype "passive"))
      (node (ref "J24_A") (pin "7") (pinfunction "7_7") (pintype "passive"))
    )
    (net (code "138") (name "/VD5") (class "Default")
      (node (ref "J1") (pin "17") (pinfunction "17_17") (pintype "passive"))
      (node (ref "J24_A") (pin "8") (pinfunction "8_8") (pintype "passive"))
    )
    (net (code "139") (name "/VD6") (class "Default")
      (node (ref "J1") (pin "16") (pinfunction "16_16") (pintype "passive"))
      (node (ref "J24_A") (pin "9") (pinfunction "9_9") (pintype "passive"))
    )
    (net (code "140") (name "/VD7") (class "Default")
      (node (ref "J1") (pin "15") (pinfunction "15_15") (pintype "passive"))
      (node (ref "J24_A") (pin "10") (pinfunction "10_10") (pintype "passive"))
    )
    (net (code "141") (name "/VD8") (class "Default")
      (node (ref "J24_A") (pin "12") (pinfunction "12_12") (pintype "passive"))
      (node (ref "J4") (pin "27") (pinfunction "27_27") (pintype "passive"))
    )
    (net (code "142") (name "/VD9") (class "Default")
      (node (ref "J24_A") (pin "13") (pinfunction "13_13") (pintype "passive"))
      (node (ref "J4") (pin "28") (pinfunction "28_28") (pintype "passive"))
    )
    (net (code "143") (name "/VD10") (class "Default")
      (node (ref "J1") (pin "14") (pinfunction "14_14") (pintype "passive"))
      (node (ref "J24_A") (pin "14") (pinfunction "14_14") (pintype "passive"))
    )
    (net (code "144") (name "/VD11") (class "Default")
      (node (ref "J1") (pin "13") (pinfunction "13_13") (pintype "passive"))
      (node (ref "J24_A") (pin "15") (pinfunction "15_15") (pintype "passive"))
    )
    (net (code "145") (name "/VD12") (class "Default")
      (node (ref "J1") (pin "12") (pinfunction "12_12") (pintype "passive"))
      (node (ref "J24_A") (pin "16") (pinfunction "16_16") (pintype "passive"))
    )
    (net (code "146") (name "/VD13") (class "Default")
      (node (ref "J1") (pin "11") (pinfunction "11_11") (pintype "passive"))
      (node (ref "J24_A") (pin "17") (pinfunction "17_17") (pintype "passive"))
    )
    (net (code "147") (name "/VD14") (class "Default")
      (node (ref "J1") (pin "10") (pinfunction "10_10") (pintype "passive"))
      (node (ref "J24_A") (pin "18") (pinfunction "18_18") (pintype "passive"))
    )
    (net (code "148") (name "/VD15") (class "Default")
      (node (ref "J1") (pin "9") (pinfunction "9_9") (pintype "passive"))
      (node (ref "J24_A") (pin "19") (pinfunction "19_19") (pintype "passive"))
    )
    (net (code "149") (name "/VD16") (class "Default")
      (node (ref "J24_B") (pin "1") (pinfunction "1_1") (pintype "passive"))
      (node (ref "J4") (pin "29") (pinfunction "29_29") (pintype "passive"))
    )
    (net (code "150") (name "/VD17") (class "Default")
      (node (ref "J24_B") (pin "2") (pinfunction "2_2") (pintype "passive"))
      (node (ref "J4") (pin "30") (pinfunction "30_30") (pintype "passive"))
    )
    (net (code "151") (name "/VD18") (class "Default")
      (node (ref "J1") (pin "8") (pinfunction "8_8") (pintype "passive"))
      (node (ref "J24_B") (pin "3") (pinfunction "3_3") (pintype "passive"))
    )
    (net (code "152") (name "/VD19") (class "Default")
      (node (ref "J1") (pin "7") (pinfunction "7_7") (pintype "passive"))
      (node (ref "J24_B") (pin "4") (pinfunction "4_4") (pintype "passive"))
    )
    (net (code "153") (name "/VD20") (class "Default")
      (node (ref "J1") (pin "6") (pinfunction "6_6") (pintype "passive"))
      (node (ref "J24_B") (pin "5") (pinfunction "5_5") (pintype "passive"))
    )
    (net (code "154") (name "/VD21") (class "Default")
      (node (ref "J1") (pin "5") (pinfunction "5_5") (pintype "passive"))
      (node (ref "J24_B") (pin "6") (pinfunction "6_6") (pintype "passive"))
    )
    (net (code "155") (name "/VD22") (class "Default")
      (node (ref "J1") (pin "4") (pinfunction "4_4") (pintype "passive"))
      (node (ref "J24_B") (pin "7") (pinfunction "7_7") (pintype "passive"))
    )
    (net (code "156") (name "/VD23") (class "Default")
      (node (ref "J1") (pin "3") (pinfunction "3_3") (pintype "passive"))
      (node (ref "J24_B") (pin "8") (pinfunction "8_8") (pintype "passive"))
    )
    (net (code "157") (name "/VDD_D1") (class "Default")
      (node (ref "J12") (pin "15") (pinfunction "15_15") (pintype "passive"))
    )
    (net (code "158") (name "/VDEN") (class "Default")
      (node (ref "J1") (pin "21") (pinfunction "21_21") (pintype "passive"))
      (node (ref "J24_B") (pin "13") (pinfunction "13_13") (pintype "passive"))
    )
    (net (code "159") (name "/VSYNC") (class "Default")
      (node (ref "J1") (pin "23") (pinfunction "23_23") (pintype "passive"))
      (node (ref "J24_B") (pin "14") (pinfunction "14_14") (pintype "passive"))
    )
    (net (code "160") (name "/WAITn") (class "Default")
      (node (ref "J3") (pin "41") (pinfunction "41_41") (pintype "passive"))
      (node (ref "R2") (pin "1") (pinfunction "1_1") (pintype "passive"))
    )
    (net (code "161") (name "/WEn") (class "Default")
      (node (ref "J3") (pin "43") (pinfunction "43_43") (pintype "passive"))
      (node (ref "U2") (pin "36") (pinfunction "IOW#_36") (pintype "passive"))
    )
    (net (code "162") (name "/XadcAIN6_YM") (class "Default")
      (node (ref "J1") (pin "38") (pinfunction "38_38") (pintype "passive"))
    )
    (net (code "163") (name "/XadcAIN8_XM") (class "Default")
      (node (ref "J1") (pin "36") (pinfunction "36_36") (pintype "passive"))
    )
    (net (code "164") (name "/XadcAIN9_XP") (class "Default")
      (node (ref "J1") (pin "35") (pinfunction "35_35") (pintype "passive"))
    )
    (net (code "165") (name "/XadcAIN9_YP") (class "Default")
      (node (ref "J1") (pin "37") (pinfunction "37_37") (pintype "passive"))
    )
    (net (code "166") (name "/host3D+") (class "Default")
      (node (ref "R104") (pin "2") (pinfunction "2_2") (pintype "passive"))
      (node (ref "R108") (pin "1") (pinfunction "1_1") (pintype "passive"))
      (node (ref "R110") (pin "1") (pinfunction "1_1") (pintype "passive"))
    )
    (net (code "167") (name "/host3D-") (class "Default")
      (node (ref "R103") (pin "2") (pinfunction "2_2") (pintype "passive"))
      (node (ref "R105") (pin "1") (pinfunction "1_1") (pintype "passive"))
      (node (ref "R109") (pin "1") (pinfunction "1_1") (pintype "passive"))
    )
    (net (code "168") (name "/host4D+") (class "Default")
      (node (ref "R115") (pin "2") (pinfunction "2_2") (pintype "passive"))
      (node (ref "U9") (pin "7") (pinfunction "DP3_7") (pintype "passive"))
    )
    (net (code "169") (name "/host4D-") (class "Default")
      (node (ref "R114") (pin "2") (pinfunction "2_2") (pintype "passive"))
      (node (ref "U9") (pin "6") (pinfunction "DM3_6") (pintype "passive"))
    )
    (net (code "170") (name "/nRSTOUT") (class "Default")
      (node (ref "J14") (pin "17") (pinfunction "17_17") (pintype "passive"))
      (node (ref "J24_B") (pin "12") (pinfunction "12_12") (pintype "passive"))
      (node (ref "J3") (pin "42") (pinfunction "42_42") (pintype "passive"))
      (node (ref "U2") (pin "40") (pinfunction "PWRST#_40") (pintype "passive"))
    )
    (net (code "171") (name "AGND") (class "Default")
      (node (ref "B5") (pin "1") (pinfunction "1_1") (pintype "passive"))
      (node (ref "C24") (pin "1") (pinfunction "1_1") (pintype "passive"))
      (node (ref "C25") (pin "1") (pinfunction "1_1") (pintype "passive"))
      (node (ref "C27") (pin "1") (pinfunction "1_1") (pintype "passive"))
      (node (ref "C29") (pin "1") (pinfunction "1_1") (pintype "passive"))
      (node (ref "C31") (pin "2") (pinfunction "2_2") (pintype "passive"))
      (node (ref "C32") (pin "2") (pinfunction "2_2") (pintype "passive"))
      (node (ref "C33") (pin "2") (pinfunction "2_2") (pintype "passive"))
      (node (ref "C34") (pin "2") (pinfunction "2_2") (pintype "passive"))
      (node (ref "C35") (pin "2") (pinfunction "2_2") (pintype "passive"))
      (node (ref "C36") (pin "2") (pinfunction "2_2") (pintype "passive"))
      (node (ref "C37") (pin "1") (pinfunction "1_1") (pintype "passive"))
      (node (ref "C38") (pin "1") (pinfunction "1_1") (pintype "passive"))
      (node (ref "C39") (pin "1") (pinfunction "1_1") (pintype "passive"))
      (node (ref "C40") (pin "1") (pinfunction "1_1") (pintype "passive"))
      (node (ref "C41") (pin "1") (pinfunction "1_1") (pintype "passive"))
      (node (ref "C42") (pin "2") (pinfunction "2_2") (pintype "passive"))
      (node (ref "C43") (pin "2") (pinfunction "2_2") (pintype "passive"))
      (node (ref "C44") (pin "1") (pinfunction "1_1") (pintype "passive"))
      (node (ref "J11") (pin "1") (pinfunction "1_1") (pintype "passive"))
      (node (ref "JC1") (pin "1") (pinfunction "1_1") (pintype "passive"))
      (node (ref "JC2") (pin "2") (pinfunction "2_2") (pintype "passive"))
      (node (ref "R14") (pin "1") (pinfunction "1_1") (pintype "passive"))
      (node (ref "R16") (pin "1") (pinfunction "1_1") (pintype "passive"))
      (node (ref "R18") (pin "2") (pinfunction "2_2") (pintype "passive"))
      (node (ref "U3") (pin "20") (pinfunction "SPKGND2_20") (pintype "passive"))
      (node (ref "U3") (pin "24") (pinfunction "SPKGND1_24") (pintype "passive"))
      (node (ref "U3") (pin "28") (pinfunction "AGND_28") (pintype "passive"))
    )
    (net (code "172") (name "GND") (class "Default")
      (node (ref "B5") (pin "2") (pinfunction "2_2") (pintype "passive"))
      (node (ref "BT1") (pin "2") (pinfunction "-_2") (pintype "passive"))
      (node (ref "C1") (pin "1") (pinfunction "1_1") (pintype "passive"))
      (node (ref "C10") (pin "2") (pinfunction "2_2") (pintype "passive"))
      (node (ref "C11") (pin "2") (pinfunction "2_2") (pintype "passive"))
      (node (ref "C12") (pin "2") (pinfunction "2_2") (pintype "passive"))
      (node (ref "C13") (pin "1") (pinfunction "1_1") (pintype "passive"))
      (node (ref "C13") (pin "2") (pinfunction "2_2") (pintype "passive"))
      (node (ref "C18") (pin "2") (pinfunction "2_2") (pintype "passive"))
      (node (ref "C19") (pin "2") (pinfunction "2_2") (pintype "passive"))
      (node (ref "C2") (pin "2") (pinfunction "2_2") (pintype "passive"))
      (node (ref "C20") (pin "1") (pinfunction "1_1") (pintype "passive"))
      (node (ref "C21") (pin "1") (pinfunction "1_1") (pintype "passive"))
      (node (ref "C22") (pin "1") (pinfunction "1_1") (pintype "passive"))
      (node (ref "C23") (pin "1") (pinfunction "1_1") (pintype "passive"))
      (node (ref "C3") (pin "1") (pinfunction "1_1") (pintype "passive"))
      (node (ref "C45") (pin "2") (pinfunction "2_2") (pintype "passive"))
      (node (ref "C46") (pin "2") (pinfunction "2_2") (pintype "passive"))
      (node (ref "C47") (pin "2") (pinfunction "2_2") (pintype "passive"))
      (node (ref "C48") (pin "2") (pinfunction "2_2") (pintype "passive"))
      (node (ref "C8") (pin "1") (pinfunction "1_1") (pintype "passive"))
      (node (ref "C83") (pin "2") (pinfunction "2_2") (pintype "passive"))
      (node (ref "C84") (pin "2") (pinfunction "2_2") (pintype "passive"))
      (node (ref "C85") (pin "2") (pinfunction "2_2") (pintype "passive"))
      (node (ref "C86") (pin "2") (pinfunction "2_2") (pintype "passive"))
      (node (ref "C87") (pin "2") (pinfunction "2_2") (pintype "passive"))
      (node (ref "C88") (pin "2") (pinfunction "2_2") (pintype "passive"))
      (node (ref "C89") (pin "2") (pinfunction "2_2") (pintype "passive"))
      (node (ref "C9") (pin "1") (pinfunction "1_1") (pintype "passive"))
      (node (ref "C90") (pin "2") (pinfunction "2_2") (pintype "passive"))
      (node (ref "C91") (pin "2") (pinfunction "2_2") (pintype "passive"))
      (node (ref "CT1") (pin "2") (pinfunction "2_2") (pintype "passive"))
      (node (ref "D1") (pin "2") (pinfunction "K_2") (pintype "passive"))
      (node (ref "J1") (pin "2") (pinfunction "2_2") (pintype "passive"))
      (node (ref "J12") (pin "20") (pinfunction "20_20") (pintype "passive"))
      (node (ref "J13") (pin "5") (pinfunction "GND_5") (pintype "passive"))
      (node (ref "J13") (pin "6") (pinfunction "6_6") (pintype "passive"))
      (node (ref "J13") (pin "7") (pinfunction "7_7") (pintype "passive"))
      (node (ref "J13") (pin "8") (pinfunction "8_8") (pintype "passive"))
      (node (ref "J13") (pin "9") (pinfunction "9_9") (pintype "passive"))
      (node (ref "J14") (pin "1") (pinfunction "1_1") (pintype "passive"))
      (node (ref "J14") (pin "19") (pinfunction "19_19") (pintype "passive"))
      (node (ref "J16") (pin "2") (pinfunction "2_2") (pintype "passive"))
      (node (ref "J17") (pin "13") (pinfunction "13_13") (pintype "passive"))
      (node (ref "J18") (pin "4") (pinfunction "4_4") (pintype "passive"))
      (node (ref "J20") (pin "4") (pinfunction "4_4") (pintype "passive"))
      (node (ref "J22") (pin "4") (pinfunction "4_4") (pintype "passive"))
      (node (ref "J24_A") (pin "11") (pinfunction "11_11") (pintype "passive"))
      (node (ref "J24_A") (pin "20") (pinfunction "20_20") (pintype "passive"))
      (node (ref "J24_B") (pin "9") (pinfunction "9_9") (pintype "passive"))
      (node (ref "J28") (pin "10") (pinfunction "10_10") (pintype "passive"))
      (node (ref "J28") (pin "11") (pinfunction "11_11") (pintype "passive"))
      (node (ref "J28") (pin "12") (pinfunction "12_12") (pintype "passive"))
      (node (ref "J28") (pin "4") (pinfunction "GND_4") (pintype "passive"))
      (node (ref "J28") (pin "8") (pinfunction "GND_8") (pintype "passive"))
      (node (ref "J28") (pin "9") (pinfunction "9_9") (pintype "passive"))
      (node (ref "J4") (pin "20") (pinfunction "20_20") (pintype "passive"))
      (node (ref "J5") (pin "1") (pinfunction "1_1") (pintype "passive"))
      (node (ref "J5") (pin "2") (pinfunction "2_2") (pintype "passive"))
      (node (ref "J5") (pin "31") (pinfunction "31_31") (pintype "passive"))
      (node (ref "J5") (pin "32") (pinfunction "32_32") (pintype "passive"))
      (node (ref "J5") (pin "33") (pinfunction "33_33") (pintype "passive"))
      (node (ref "J5") (pin "34") (pinfunction "34_34") (pintype "passive"))
      (node (ref "J9") (pin "8") (pinfunction "CHS_GND_8") (pintype "passive"))
      (node (ref "K1") (pin "1") (pinfunction "1_1") (pintype "passive"))
      (node (ref "K2") (pin "2") (pinfunction "2_2") (pintype "passive"))
      (node (ref "K3") (pin "2") (pinfunction "2_2") (pintype "passive"))
      (node (ref "K4") (pin "2") (pinfunction "2_2") (pintype "passive"))
      (node (ref "K5") (pin "2") (pinfunction "2_2") (pintype "passive"))
      (node (ref "K6") (pin "2") (pinfunction "2_2") (pintype "passive"))
      (node (ref "K7") (pin "2") (pinfunction "2_2") (pintype "passive"))
      (node (ref "K8") (pin "2") (pinfunction "2_2") (pintype "passive"))
      (node (ref "K9") (pin "2") (pinfunction "2_2") (pintype "passive"))
      (node (ref "Q1") (pin "3") (pinfunction "E_3") (pintype "passive"))
      (node (ref "R10") (pin "1") (pinfunction "1_1") (pintype "passive"))
      (node (ref "R106") (pin "1") (pinfunction "1_1") (pintype "passive"))
      (node (ref "R107") (pin "1") (pinfunction "1_1") (pintype "passive"))
      (node (ref "R116") (pin "1") (pinfunction "1_1") (pintype "passive"))
      (node (ref "R117") (pin "1") (pinfunction "1_1") (pintype "passive"))
      (node (ref "R118") (pin "1") (pinfunction "1_1") (pintype "passive"))
      (node (ref "R119") (pin "1") (pinfunction "1_1") (pintype "passive"))
      (node (ref "SW-1") (pin "3") (pinfunction "3_3") (pintype "passive"))
      (node (ref "SW-1") (pin "5") (pinfunction "5_5") (pintype "passive"))
      (node (ref "SW-2") (pin "3") (pinfunction "3_3") (pintype "passive"))
      (node (ref "SW-2") (pin "4") (pinfunction "4_4") (pintype "passive"))
      (node (ref "SW-2") (pin "5") (pinfunction "5_5") (pintype "passive"))
      (node (ref "U1") (pin "1") (pinfunction "GND_1") (pintype "passive"))
      (node (ref "U2") (pin "15") (pinfunction "GND1_15") (pintype "passive"))
      (node (ref "U2") (pin "33") (pinfunction "GND2_33") (pintype "passive"))
      (node (ref "U2") (pin "41") (pinfunction "TEST_41") (pintype "passive"))
      (node (ref "U2") (pin "45") (pinfunction "GND0_45") (pintype "passive"))
      (node (ref "U2") (pin "47") (pinfunction "AGND3_47") (pintype "passive"))
      (node (ref "U2") (pin "48") (pinfunction "BGGND_48") (pintype "passive"))
      (node (ref "U2") (pin "5") (pinfunction "AGND1_5") (pintype "passive"))
      (node (ref "U2") (pin "6") (pinfunction "AGND0_6") (pintype "passive"))
      (node (ref "U3") (pin "9") (pinfunction "DGND_9") (pintype "passive"))
      (node (ref "U9") (pin "1") (pinfunction "VSS_1") (pintype "passive"))
    )
    (net (code "173") (name "MICBIAS") (class "Default")
      (node (ref "B4") (pin "2") (pinfunction "2_2") (pintype "passive"))
      (node (ref "R15") (pin "1") (pinfunction "1_1") (pintype "passive"))
    )
    (net (code "174") (name "Net-(BT1-+)") (class "Default")
      (node (ref "BT1") (pin "1") (pinfunction "+_1") (pintype "passive"))
      (node (ref "R21") (pin "2") (pinfunction "2_2") (pintype "passive"))
    )
    (net (code "175") (name "Net-(BZ1-Pad1)") (class "Default")
      (node (ref "BZ1") (pin "1") (pinfunction "1_1") (pintype "passive"))
      (node (ref "R19") (pin "1") (pinfunction "1_1") (pintype "passive"))
    )
    (net (code "176") (name "Net-(C11-Pad1)") (class "Default")
      (node (ref "C11") (pin "1") (pinfunction "1_1") (pintype "passive"))
      (node (ref "R6") (pin "1") (pinfunction "1_1") (pintype "passive"))
      (node (ref "R7") (pin "1") (pinfunction "1_1") (pintype "passive"))
    )
    (net (code "177") (name "Net-(C12-Pad1)") (class "Default")
      (node (ref "C12") (pin "1") (pinfunction "1_1") (pintype "passive"))
      (node (ref "R8") (pin "1") (pinfunction "1_1") (pintype "passive"))
      (node (ref "R9") (pin "1") (pinfunction "1_1") (pintype "passive"))
    )
    (net (code "178") (name "Net-(C26-Pad2)") (class "Default")
      (node (ref "C26") (pin "2") (pinfunction "2_2") (pintype "passive"))
      (node (ref "C27") (pin "2") (pinfunction "2_2") (pintype "passive"))
      (node (ref "JC1") (pin "4") (pinfunction "4_4") (pintype "passive"))
      (node (ref "R14") (pin "2") (pinfunction "2_2") (pintype "passive"))
    )
    (net (code "179") (name "Net-(C28-Pad2)") (class "Default")
      (node (ref "C28") (pin "2") (pinfunction "2_2") (pintype "passive"))
      (node (ref "C29") (pin "2") (pinfunction "2_2") (pintype "passive"))
      (node (ref "JC1") (pin "2") (pinfunction "2_2") (pintype "passive"))
      (node (ref "R16") (pin "2") (pinfunction "2_2") (pintype "passive"))
    )
    (net (code "180") (name "Net-(C30-Pad2)") (class "Default")
      (node (ref "C30") (pin "2") (pinfunction "2_2") (pintype "passive"))
      (node (ref "C37") (pin "2") (pinfunction "2_2") (pintype "passive"))
      (node (ref "JC2") (pin "1") (pinfunction "1_1") (pintype "passive"))
      (node (ref "R15") (pin "2") (pinfunction "2_2") (pintype "passive"))
      (node (ref "R17") (pin "1") (pinfunction "1_1") (pintype "passive"))
      (node (ref "R18") (pin "1") (pinfunction "1_1") (pintype "passive"))
    )
    (net (code "181") (name "Net-(D1-A)") (class "Default")
      (node (ref "D1") (pin "1") (pinfunction "A_1") (pintype "passive"))
      (node (ref "R3") (pin "2") (pinfunction "2_2") (pintype "passive"))
    )
    (net (code "182") (name "Net-(D3-A)") (class "Default")
      (node (ref "D3") (pin "1") (pinfunction "A_1") (pintype "passive"))
      (node (ref "R41") (pin "2") (pinfunction "2_2") (pintype "passive"))
    )
    (net (code "183") (name "Net-(D3-K)") (class "Default")
      (node (ref "D3") (pin "2") (pinfunction "K_2") (pintype "passive"))
      (node (ref "J17") (pin "11") (pinfunction "11_11") (pintype "passive"))
      (node (ref "R42") (pin "2") (pinfunction "2_2") (pintype "passive"))
      (node (ref "RA1/2") (pin "9") (pinfunction "9_9") (pintype "passive"))
    )
    (net (code "184") (name "Net-(J8-Pad1)") (class "Default")
      (node (ref "J8") (pin "1") (pinfunction "1_1") (pintype "passive"))
      (node (ref "SW-1") (pin "1") (pinfunction "1_1") (pintype "passive"))
    )
    (net (code "185") (name "Net-(J8-Pad2)") (class "Default")
      (node (ref "J8") (pin "2") (pinfunction "2_2") (pintype "passive"))
      (node (ref "SW-1") (pin "4") (pinfunction "4_4") (pintype "passive"))
    )
    (net (code "186") (name "Net-(J9-LEDG+)") (class "Default")
      (node (ref "J9") (pin "9") (pinfunction "LEDG+_9") (pintype "passive"))
      (node (ref "R4") (pin "1") (pinfunction "1_1") (pintype "passive"))
    )
    (net (code "187") (name "Net-(J9-LEDY+)") (class "Default")
      (node (ref "J9") (pin "12") (pinfunction "LEDY+_12") (pintype "passive"))
      (node (ref "R5") (pin "1") (pinfunction "1_1") (pintype "passive"))
    )
    (net (code "188") (name "Net-(J11-Pad2)") (class "Default")
      (node (ref "J11") (pin "2") (pinfunction "2_2") (pintype "passive"))
      (node (ref "R17") (pin "2") (pinfunction "2_2") (pintype "passive"))
    )
    (net (code "189") (name "Net-(J16-Pad12)") (class "Default")
      (node (ref "J16") (pin "12") (pinfunction "12_12") (pintype "passive"))
      (node (ref "R28") (pin "1") (pinfunction "1_1") (pintype "passive"))
    )
    (net (code "190") (name "Net-(J16-Pad14)") (class "Default")
      (node (ref "J16") (pin "14") (pinfunction "14_14") (pintype "passive"))
      (node (ref "R29") (pin "1") (pinfunction "1_1") (pintype "passive"))
    )
    (net (code "191") (name "Net-(J16-Pad16)") (class "Default")
      (node (ref "J16") (pin "16") (pinfunction "16_16") (pintype "passive"))
      (node (ref "R30") (pin "1") (pinfunction "1_1") (pintype "passive"))
    )
    (net (code "192") (name "Net-(J16-Pad18)") (class "Default")
      (node (ref "J16") (pin "18") (pinfunction "18_18") (pintype "passive"))
      (node (ref "R31") (pin "1") (pinfunction "1_1") (pintype "passive"))
    )
    (net (code "193") (name "Net-(J16-Pad20)") (class "Default")
      (node (ref "J16") (pin "20") (pinfunction "20_20") (pintype "passive"))
      (node (ref "R32") (pin "1") (pinfunction "1_1") (pintype "passive"))
    )
    (net (code "194") (name "Net-(J17-CD{slash}DATA3)") (class "Default")
      (node (ref "J17") (pin "1") (pinfunction "CD/DATA3_1") (pintype "passive"))
      (node (ref "R49") (pin "2") (pinfunction "2_2") (pintype "passive"))
      (node (ref "RA1/2") (pin "15") (pinfunction "15_15") (pintype "passive"))
    )
    (net (code "195") (name "Net-(J17-CLK)") (class "Default")
      (node (ref "J17") (pin "5") (pinfunction "CLK_5") (pintype "passive"))
      (node (ref "R44") (pin "2") (pinfunction "2_2") (pintype "passive"))
      (node (ref "RA1/2") (pin "13") (pinfunction "13_13") (pintype "passive"))
    )
    (net (code "196") (name "Net-(J17-CMD)") (class "Default")
      (node (ref "J17") (pin "2") (pinfunction "CMD_2") (pintype "passive"))
      (node (ref "R45") (pin "2") (pinfunction "2_2") (pintype "passive"))
      (node (ref "RA1/2") (pin "14") (pinfunction "14_14") (pintype "passive"))
    )
    (net (code "197") (name "Net-(J17-DATA0)") (class "Default")
      (node (ref "J17") (pin "7") (pinfunction "DATA0_7") (pintype "passive"))
      (node (ref "R46") (pin "2") (pinfunction "2_2") (pintype "passive"))
      (node (ref "RA1/2") (pin "12") (pinfunction "12_12") (pintype "passive"))
    )
    (net (code "198") (name "Net-(J17-DATA1)") (class "Default")
      (node (ref "J17") (pin "8") (pinfunction "DATA1_8") (pintype "passive"))
      (node (ref "R47") (pin "2") (pinfunction "2_2") (pintype "passive"))
      (node (ref "RA1/2") (pin "11") (pinfunction "11_11") (pintype "passive"))
    )
    (net (code "199") (name "Net-(J17-DATA2)") (class "Default")
      (node (ref "J17") (pin "9") (pinfunction "DATA2_9") (pintype "passive"))
      (node (ref "R48") (pin "2") (pinfunction "2_2") (pintype "passive"))
      (node (ref "RA1/2") (pin "16") (pinfunction "16_16") (pintype "passive"))
    )
    (net (code "200") (name "Net-(J17-Pad10)") (class "Default")
      (node (ref "J17") (pin "10") (pinfunction "10_10") (pintype "passive"))
      (node (ref "R43") (pin "2") (pinfunction "2_2") (pintype "passive"))
      (node (ref "RA1/2") (pin "10") (pinfunction "10_10") (pintype "passive"))
    )
    (net (code "201") (name "Net-(J17-VDD)") (class "Default")
      (node (ref "C49") (pin "1") (pinfunction "1_1") (pintype "passive"))
      (node (ref "J17") (pin "4") (pinfunction "VDD_4") (pintype "passive"))
      (node (ref "R41") (pin "1") (pinfunction "1_1") (pintype "passive"))
      (node (ref "R42") (pin "1") (pinfunction "1_1") (pintype "passive"))
      (node (ref "R43") (pin "1") (pinfunction "1_1") (pintype "passive"))
      (node (ref "R44") (pin "1") (pinfunction "1_1") (pintype "passive"))
      (node (ref "R45") (pin "1") (pinfunction "1_1") (pintype "passive"))
      (node (ref "R46") (pin "1") (pinfunction "1_1") (pintype "passive"))
      (node (ref "R47") (pin "1") (pinfunction "1_1") (pintype "passive"))
      (node (ref "R48") (pin "1") (pinfunction "1_1") (pintype "passive"))
      (node (ref "R49") (pin "1") (pinfunction "1_1") (pintype "passive"))
    )
    (net (code "202") (name "Net-(J17-VSS1)") (class "Default")
      (node (ref "C49") (pin "2") (pinfunction "2_2") (pintype "passive"))
      (node (ref "J17") (pin "12") (pinfunction "12_12") (pintype "passive"))
      (node (ref "J17") (pin "3") (pinfunction "VSS1_3") (pintype "passive"))
      (node (ref "J17") (pin "6") (pinfunction "VSS2_6") (pintype "passive"))
    )
    (net (code "203") (name "Net-(J24_B-Pad10)") (class "Default")
      (node (ref "J24_B") (pin "10") (pinfunction "10_10") (pintype "passive"))
      (node (ref "R84") (pin "2") (pinfunction "2_2") (pintype "passive"))
    )
    (net (code "204") (name "Net-(J24_B-Pad17)") (class "Default")
      (node (ref "J24_B") (pin "17") (pinfunction "17_17") (pintype "passive"))
      (node (ref "R90") (pin "2") (pinfunction "2_2") (pintype "passive"))
    )
    (net (code "205") (name "Net-(J24_B-Pad18)") (class "Default")
      (node (ref "J24_B") (pin "18") (pinfunction "18_18") (pintype "passive"))
      (node (ref "R92") (pin "2") (pinfunction "2_2") (pintype "passive"))
    )
    (net (code "206") (name "Net-(J24_B-Pad19)") (class "Default")
      (node (ref "J24_B") (pin "19") (pinfunction "19_19") (pintype "passive"))
      (node (ref "R93") (pin "2") (pinfunction "2_2") (pintype "passive"))
    )
    (net (code "207") (name "Net-(J24_B-Pad20)") (class "Default")
      (node (ref "J24_B") (pin "20") (pinfunction "20_20") (pintype "passive"))
      (node (ref "R94") (pin "2") (pinfunction "2_2") (pintype "passive"))
    )
    (net (code "208") (name "Net-(J28-VCC-Pad1)") (class "Default")
      (node (ref "J28") (pin "1") (pinfunction "VCC_1") (pintype "passive"))
      (node (ref "L5") (pin "1") (pinfunction "1_1") (pintype "passive"))
    )
    (net (code "209") (name "Net-(J28-VCC-Pad5)") (class "Default")
      (node (ref "J28") (pin "5") (pinfunction "VCC_5") (pintype "passive"))
      (node (ref "L6") (pin "1") (pinfunction "1_1") (pintype "passive"))
    )
    (net (code "210") (name "Net-(K2-Pad1)") (class "Default")
      (node (ref "K2") (pin "1") (pinfunction "1_1") (pintype "passive"))
      (node (ref "R33") (pin "2") (pinfunction "2_2") (pintype "passive"))
      (node (ref "R51") (pin "2") (pinfunction "2_2") (pintype "passive"))
    )
    (net (code "211") (name "Net-(K3-Pad1)") (class "Default")
      (node (ref "K3") (pin "1") (pinfunction "1_1") (pintype "passive"))
      (node (ref "R34") (pin "2") (pinfunction "2_2") (pintype "passive"))
      (node (ref "R53") (pin "2") (pinfunction "2_2") (pintype "passive"))
    )
    (net (code "212") (name "Net-(K4-Pad1)") (class "Default")
      (node (ref "K4") (pin "1") (pinfunction "1_1") (pintype "passive"))
      (node (ref "R35") (pin "2") (pinfunction "2_2") (pintype "passive"))
      (node (ref "R54") (pin "2") (pinfunction "2_2") (pintype "passive"))
    )
    (net (code "213") (name "Net-(K5-Pad1)") (class "Default")
      (node (ref "K5") (pin "1") (pinfunction "1_1") (pintype "passive"))
      (node (ref "R36") (pin "2") (pinfunction "2_2") (pintype "passive"))
      (node (ref "R55") (pin "2") (pinfunction "2_2") (pintype "passive"))
    )
    (net (code "214") (name "Net-(K6-Pad1)") (class "Default")
      (node (ref "K6") (pin "1") (pinfunction "1_1") (pintype "passive"))
      (node (ref "R37") (pin "2") (pinfunction "2_2") (pintype "passive"))
      (node (ref "R56") (pin "2") (pinfunction "2_2") (pintype "passive"))
    )
    (net (code "215") (name "Net-(K7-Pad1)") (class "Default")
      (node (ref "K7") (pin "1") (pinfunction "1_1") (pintype "passive"))
      (node (ref "R38") (pin "2") (pinfunction "2_2") (pintype "passive"))
      (node (ref "R57") (pin "2") (pinfunction "2_2") (pintype "passive"))
    )
    (net (code "216") (name "Net-(K8-Pad1)") (class "Default")
      (node (ref "K8") (pin "1") (pinfunction "1_1") (pintype "passive"))
      (node (ref "R39") (pin "2") (pinfunction "2_2") (pintype "passive"))
      (node (ref "R58") (pin "2") (pinfunction "2_2") (pintype "passive"))
    )
    (net (code "217") (name "Net-(K9-Pad1)") (class "Default")
      (node (ref "K9") (pin "1") (pinfunction "1_1") (pintype "passive"))
      (node (ref "R40") (pin "2") (pinfunction "2_2") (pintype "passive"))
      (node (ref "R59") (pin "2") (pinfunction "2_2") (pintype "passive"))
    )
    (net (code "218") (name "Net-(Q1-B)") (class "Default")
      (node (ref "Q1") (pin "2") (pinfunction "B_2") (pintype "passive"))
      (node (ref "R20") (pin "1") (pinfunction "1_1") (pintype "passive"))
    )
    (net (code "219") (name "Net-(Q1-C)") (class "Default")
      (node (ref "BZ1") (pin "2") (pinfunction "2_2") (pintype "passive"))
      (node (ref "Q1") (pin "1") (pinfunction "C_1") (pintype "passive"))
    )
    (net (code "220") (name "Net-(R1-Pad2)") (class "Default")
      (node (ref "R1") (pin "2") (pinfunction "2_2") (pintype "passive"))
      (node (ref "SW-2") (pin "2") (pinfunction "2_2") (pintype "passive"))
    )
    (net (code "221") (name "Net-(U2-BGRES)") (class "Default")
      (node (ref "R10") (pin "2") (pinfunction "2_2") (pintype "passive"))
      (node (ref "U2") (pin "1") (pinfunction "BGRES_1") (pintype "passive"))
    )
    (net (code "222") (name "Net-(U2-X1)") (class "Default")
      (node (ref "C18") (pin "1") (pinfunction "1_1") (pintype "passive"))
      (node (ref "U2") (pin "44") (pinfunction "X1_44") (pintype "passive"))
      (node (ref "Y1") (pin "2") (pinfunction "OSC2_2") (pintype "passive"))
    )
    (net (code "223") (name "Net-(U2-X2)") (class "Default")
      (node (ref "C19") (pin "1") (pinfunction "1_1") (pintype "passive"))
      (node (ref "U2") (pin "43") (pinfunction "X2_43") (pintype "passive"))
      (node (ref "Y1") (pin "1") (pinfunction "OSC1_1") (pintype "passive"))
    )
    (net (code "224") (name "Net-(U3-HP_L)") (class "Default")
      (node (ref "C26") (pin "1") (pinfunction "1_1") (pintype "passive"))
      (node (ref "U3") (pin "31") (pinfunction "HP_L_31") (pintype "passive"))
    )
    (net (code "225") (name "Net-(U3-HP_R)") (class "Default")
      (node (ref "C28") (pin "1") (pinfunction "1_1") (pintype "passive"))
      (node (ref "U3") (pin "29") (pinfunction "HP_R_29") (pintype "passive"))
    )
    (net (code "226") (name "Net-(U3-LINPUT1)") (class "Default")
      (node (ref "C30") (pin "1") (pinfunction "1_1") (pintype "passive"))
      (node (ref "U3") (pin "4") (pinfunction "LINPUT1_4") (pintype "passive"))
    )
    (net (code "227") (name "Net-(U3-LINPUT2)") (class "Default")
      (node (ref "C38") (pin "2") (pinfunction "2_2") (pintype "passive"))
      (node (ref "U3") (pin "3") (pinfunction "LINPUT2_3") (pintype "passive"))
    )
    (net (code "228") (name "Net-(U3-LINPUT3{slash}JD2)") (class "Default")
      (node (ref "C39") (pin "2") (pinfunction "2_2") (pintype "passive"))
      (node (ref "U3") (pin "2") (pinfunction "LINPUT3/JD2_2") (pintype "passive"))
    )
    (net (code "229") (name "Net-(U3-MICBIAS1)") (class "Default")
      (node (ref "B4") (pin "1") (pinfunction "1_1") (pintype "passive"))
      (node (ref "C42") (pin "1") (pinfunction "1_1") (pintype "passive"))
      (node (ref "C43") (pin "1") (pinfunction "1_1") (pintype "passive"))
      (node (ref "U3") (pin "1") (pinfunction "MICBIAS1_1") (pintype "passive"))
    )
    (net (code "230") (name "Net-(U3-RINPUT1)") (class "Default")
      (node (ref "C40") (pin "2") (pinfunction "2_2") (pintype "passive"))
      (node (ref "U3") (pin "5") (pinfunction "RINPUT1_5") (pintype "passive"))
    )
    (net (code "231") (name "Net-(U3-RINPUT2)") (class "Default")
      (node (ref "C41") (pin "2") (pinfunction "2_2") (pintype "passive"))
      (node (ref "U3") (pin "6") (pinfunction "RINPUT2_6") (pintype "passive"))
    )
    (net (code "232") (name "Net-(U3-RINPUT3{slash}JD3)") (class "Default")
      (node (ref "C44") (pin "2") (pinfunction "2_2") (pintype "passive"))
      (node (ref "U3") (pin "7") (pinfunction "RINPUT3/JD3_7") (pintype "passive"))
    )
    (net (code "233") (name "Net-(U3-VMID)") (class "Default")
      (node (ref "C31") (pin "1") (pinfunction "1_1") (pintype "passive"))
      (node (ref "C32") (pin "1") (pinfunction "1_1") (pintype "passive"))
      (node (ref "U3") (pin "27") (pinfunction "VMID_27") (pintype "passive"))
    )
    (net (code "234") (name "Net-(U9-BUSJ)") (class "Default")
      (node (ref "R111") (pin "1") (pinfunction "1_1") (pintype "passive"))
      (node (ref "U9") (pin "19") (pinfunction "BUSJ_19") (pintype "passive"))
    )
    (net (code "235") (name "Net-(U9-DM4)") (class "Default")
      (node (ref "R109") (pin "2") (pinfunction "2_2") (pintype "passive"))
      (node (ref "U9") (pin "4") (pinfunction "DM4_4") (pintype "passive"))
    )
    (net (code "236") (name "Net-(U9-DP4)") (class "Default")
      (node (ref "R110") (pin "2") (pinfunction "2_2") (pintype "passive"))
      (node (ref "U9") (pin "5") (pinfunction "DP4_5") (pintype "passive"))
    )
    (net (code "237") (name "Net-(U9-REXT)") (class "Default")
      (node (ref "R119") (pin "2") (pinfunction "2_2") (pintype "passive"))
      (node (ref "U9") (pin "14") (pinfunction "REXT_14") (pintype "passive"))
    )
    (net (code "238") (name "Net-(U9-VBUSM)") (class "Default")
      (node (ref "R113") (pin "1") (pinfunction "1_1") (pintype "passive"))
      (node (ref "R116") (pin "2") (pinfunction "2_2") (pintype "passive"))
      (node (ref "U9") (pin "18") (pinfunction "VBUSM_18") (pintype "passive"))
    )
    (net (code "239") (name "Net-(U9-XIN)") (class "Default")
      (node (ref "U9") (pin "3") (pinfunction "XIN_3") (pintype "passive"))
      (node (ref "Y2") (pin "1") (pinfunction "OSC1_1") (pintype "passive"))
    )
    (net (code "240") (name "Net-(U9-XOUT)") (class "Default")
      (node (ref "U9") (pin "2") (pinfunction "XOUT_2") (pintype "passive"))
      (node (ref "Y2") (pin "2") (pinfunction "OSC2_2") (pintype "passive"))
    )
    (net (code "241") (name "Net-(U9-XRSTJ)") (class "Default")
      (node (ref "R112") (pin "1") (pinfunction "1_1") (pintype "passive"))
      (node (ref "U9") (pin "17") (pinfunction "XRSTJ_17") (pintype "passive"))
    )
    (net (code "242") (name "VDD18_HUB") (class "Default")
      (node (ref "C86") (pin "1") (pinfunction "1_1") (pintype "passive"))
      (node (ref "C90") (pin "1") (pinfunction "1_1") (pintype "passive"))
      (node (ref "U9") (pin "12") (pinfunction "VD18_O_12") (pintype "passive"))
      (node (ref "U9") (pin "28") (pinfunction "VD18_28") (pintype "passive"))
    )
    (net (code "243") (name "VDD33_HUB") (class "Default")
      (node (ref "C87") (pin "1") (pinfunction "1_1") (pintype "passive"))
      (node (ref "C91") (pin "1") (pinfunction "1_1") (pintype "passive"))
      (node (ref "R111") (pin "2") (pinfunction "2_2") (pintype "passive"))
      (node (ref "R112") (pin "2") (pinfunction "2_2") (pintype "passive"))
      (node (ref "U9") (pin "13") (pinfunction "VD33_13") (pintype "passive"))
      (node (ref "U9") (pin "21") (pinfunction "VD33_O_21") (pintype "passive"))
      (node (ref "U9") (pin "26") (pinfunction "OVCJ_26") (pintype "passive"))
    )
    (net (code "244") (name "VDD_5V") (class "Default")
      (node (ref "B1") (pin "1") (pinfunction "1_1") (pintype "passive"))
      (node (ref "C1") (pin "2") (pinfunction "2_2") (pintype "passive"))
      (node (ref "C83") (pin "1") (pinfunction "1_1") (pintype "passive"))
      (node (ref "C85") (pin "1") (pinfunction "1_1") (pintype "passive"))
      (node (ref "C88") (pin "1") (pinfunction "1_1") (pintype "passive"))
      (node (ref "C89") (pin "1") (pinfunction "1_1") (pintype "passive"))
      (node (ref "CT1") (pin "1") (pinfunction "1_1") (pintype "passive"))
      (node (ref "J1") (pin "1") (pinfunction "1_1") (pintype "passive"))
      (node (ref "J14") (pin "2") (pinfunction "2_2") (pintype "passive"))
      (node (ref "J18") (pin "3") (pinfunction "3_3") (pintype "passive"))
      (node (ref "J20") (pin "3") (pinfunction "3_3") (pintype "passive"))
      (node (ref "J22") (pin "3") (pinfunction "3_3") (pintype "passive"))
      (node (ref "J24_A") (pin "1") (pinfunction "1_1") (pintype "passive"))
      (node (ref "J24_A") (pin "2") (pinfunction "2_2") (pintype "passive"))
      (node (ref "J5") (pin "27") (pinfunction "27_27") (pintype "passive"))
      (node (ref "J5") (pin "28") (pinfunction "28_28") (pintype "passive"))
      (node (ref "L5") (pin "2") (pinfunction "2_2") (pintype "passive"))
      (node (ref "L6") (pin "2") (pinfunction "2_2") (pintype "passive"))
      (node (ref "R113") (pin "2") (pinfunction "2_2") (pintype "passive"))
      (node (ref "R19") (pin "2") (pinfunction "2_2") (pintype "passive"))
      (node (ref "SW-1") (pin "2") (pinfunction "2_2") (pintype "passive"))
      (node (ref "U1") (pin "3") (pinfunction "VIN_3") (pintype "passive"))
      (node (ref "U9") (pin "20") (pinfunction "VDD5_20") (pintype "passive"))
    )
    (net (code "245") (name "VDD_5V-AUDIO") (class "Default")
      (node (ref "B1") (pin "2") (pinfunction "2_2") (pintype "passive"))
      (node (ref "C20") (pin "2") (pinfunction "2_2") (pintype "passive"))
      (node (ref "C21") (pin "2") (pinfunction "2_2") (pintype "passive"))
      (node (ref "U3") (pin "21") (pinfunction "SPKVDD2_21") (pintype "passive"))
      (node (ref "U3") (pin "26") (pinfunction "SPKVDD1_26") (pintype "passive"))
    )
    (net (code "246") (name "VDD_AUDIO_A3.3V") (class "Default")
      (node (ref "B3") (pin "2") (pinfunction "2_2") (pintype "passive"))
      (node (ref "C24") (pin "2") (pinfunction "2_2") (pintype "passive"))
      (node (ref "C25") (pin "2") (pinfunction "2_2") (pintype "passive"))
      (node (ref "U3") (pin "32") (pinfunction "AVDD_32") (pintype "passive"))
    )
    (net (code "247") (name "VDD_AUDIO_D3.3V") (class "Default")
      (node (ref "B2") (pin "2") (pinfunction "2_2") (pintype "passive"))
      (node (ref "C22") (pin "2") (pinfunction "2_2") (pintype "passive"))
      (node (ref "C23") (pin "2") (pinfunction "2_2") (pintype "passive"))
      (node (ref "R11") (pin "1") (pinfunction "1_1") (pintype "passive"))
      (node (ref "R12") (pin "1") (pinfunction "1_1") (pintype "passive"))
      (node (ref "R13") (pin "1") (pinfunction "1_1") (pintype "passive"))
      (node (ref "U3") (pin "10") (pinfunction "DBVDD_10") (pintype "passive"))
      (node (ref "U3") (pin "8") (pinfunction "DCVDD_8") (pintype "passive"))
    )
    (net (code "248") (name "VDD_CAM_1.8V") (class "Default")
      (node (ref "J12") (pin "19") (pinfunction "19_19") (pintype "passive"))
      (node (ref "J4") (pin "19") (pinfunction "19_19") (pintype "passive"))
    )
    (net (code "249") (name "VDD_CAM_2.8V") (class "Default")
      (node (ref "J4") (pin "18") (pinfunction "18_18") (pintype "passive"))
    )
    (net (code "250") (name "VDD_IO") (class "Default")
      (node (ref "B2") (pin "1") (pinfunction "1_1") (pintype "passive"))
      (node (ref "B3") (pin "1") (pinfunction "1_1") (pintype "passive"))
      (node (ref "C2") (pin "1") (pinfunction "1_1") (pintype "passive"))
      (node (ref "C3") (pin "2") (pinfunction "2_2") (pintype "passive"))
      (node (ref "D2") (pin "1") (pinfunction "A_1") (pintype "passive"))
      (node (ref "J12") (pin "17") (pinfunction "17_17") (pintype "passive"))
      (node (ref "J14") (pin "20") (pinfunction "20_20") (pintype "passive"))
      (node (ref "J16") (pin "1") (pinfunction "1_1") (pintype "passive"))
      (node (ref "J5") (pin "5") (pinfunction "5_5") (pintype "passive"))
      (node (ref "J5") (pin "6") (pinfunction "6_6") (pintype "passive"))
      (node (ref "R2") (pin "2") (pinfunction "2_2") (pintype "passive"))
      (node (ref "R22") (pin "2") (pinfunction "2_2") (pintype "passive"))
      (node (ref "R23") (pin "2") (pinfunction "2_2") (pintype "passive"))
      (node (ref "R24") (pin "2") (pinfunction "2_2") (pintype "passive"))
      (node (ref "R25") (pin "2") (pinfunction "2_2") (pintype "passive"))
      (node (ref "R27") (pin "2") (pinfunction "2_2") (pintype "passive"))
      (node (ref "R28") (pin "2") (pinfunction "2_2") (pintype "passive"))
      (node (ref "R29") (pin "2") (pinfunction "2_2") (pintype "passive"))
      (node (ref "R3") (pin "1") (pinfunction "1_1") (pintype "passive"))
      (node (ref "R30") (pin "2") (pinfunction "2_2") (pintype "passive"))
      (node (ref "R31") (pin "2") (pinfunction "2_2") (pintype "passive"))
      (node (ref "R32") (pin "2") (pinfunction "2_2") (pintype "passive"))
      (node (ref "R33") (pin "1") (pinfunction "1_1") (pintype "passive"))
      (node (ref "R34") (pin "1") (pinfunction "1_1") (pintype "passive"))
      (node (ref "R35") (pin "1") (pinfunction "1_1") (pintype "passive"))
      (node (ref "R36") (pin "1") (pinfunction "1_1") (pintype "passive"))
      (node (ref "R37") (pin "1") (pinfunction "1_1") (pintype "passive"))
      (node (ref "R38") (pin "1") (pinfunction "1_1") (pintype "passive"))
      (node (ref "R39") (pin "1") (pinfunction "1_1") (pintype "passive"))
      (node (ref "R4") (pin "2") (pinfunction "2_2") (pintype "passive"))
      (node (ref "R40") (pin "1") (pinfunction "1_1") (pintype "passive"))
      (node (ref "R5") (pin "2") (pinfunction "2_2") (pintype "passive"))
      (node (ref "R88") (pin "1") (pinfunction "1_1") (pintype "passive"))
      (node (ref "R89") (pin "1") (pinfunction "1_1") (pintype "passive"))
      (node (ref "SW-2") (pin "1") (pinfunction "1_1") (pintype "passive"))
      (node (ref "U1") (pin "2") (pinfunction "VOUT_2") (pintype "passive"))
      (node (ref "U1") (pin "4") (pinfunction "OV_4") (pintype "passive"))
      (node (ref "U2") (pin "23") (pinfunction "VDD0_23") (pintype "passive"))
      (node (ref "U2") (pin "30") (pinfunction "VDD1_30") (pintype "passive"))
      (node (ref "U2") (pin "42") (pinfunction "VDD2_42") (pintype "passive"))
    )
    (net (code "251") (name "VDD_RTC") (class "Default")
      (node (ref "C47") (pin "1") (pinfunction "1_1") (pintype "passive"))
      (node (ref "C48") (pin "1") (pinfunction "1_1") (pintype "passive"))
      (node (ref "D2") (pin "2") (pinfunction "K_2") (pintype "passive"))
      (node (ref "J3") (pin "4") (pinfunction "4_4") (pintype "passive"))
      (node (ref "R21") (pin "1") (pinfunction "1_1") (pintype "passive"))
    )
    (net (code "252") (name "unconnected-(C84-Pad1)") (class "Default")
      (node (ref "C84") (pin "1") (pinfunction "1_1") (pintype "passive"))
    )
    (net (code "253") (name "unconnected-(J1-Pad65)") (class "Default")
      (node (ref "J1") (pin "65") (pinfunction "65_65") (pintype "passive"))
    )
    (net (code "254") (name "unconnected-(J3-Pad2)") (class "Default")
      (node (ref "J3") (pin "2") (pinfunction "2_2") (pintype "passive"))
    )
    (net (code "255") (name "unconnected-(J3-Pad5)") (class "Default")
      (node (ref "J3") (pin "5") (pinfunction "5_5") (pintype "passive"))
    )
    (net (code "256") (name "unconnected-(J3-Pad6)") (class "Default")
      (node (ref "J3") (pin "6") (pinfunction "6_6") (pintype "passive"))
    )
    (net (code "257") (name "unconnected-(J3-Pad62)") (class "Default")
      (node (ref "J3") (pin "62") (pinfunction "62_62") (pintype "passive"))
    )
    (net (code "258") (name "unconnected-(J4-Pad17)") (class "Default")
      (node (ref "J4") (pin "17") (pinfunction "17_17") (pintype "passive"))
    )
    (net (code "259") (name "unconnected-(J5-Pad3)") (class "Default")
      (node (ref "J5") (pin "3") (pinfunction "3_3") (pintype "passive"))
    )
    (net (code "260") (name "unconnected-(J5-Pad4)") (class "Default")
      (node (ref "J5") (pin "4") (pinfunction "4_4") (pintype "passive"))
    )
    (net (code "261") (name "unconnected-(J5-Pad21)") (class "Default")
      (node (ref "J5") (pin "21") (pinfunction "21_21") (pintype "passive"))
    )
    (net (code "262") (name "unconnected-(J5-Pad22)") (class "Default")
      (node (ref "J5") (pin "22") (pinfunction "22_22") (pintype "passive"))
    )
    (net (code "263") (name "unconnected-(J5-Pad25)") (class "Default")
      (node (ref "J5") (pin "25") (pinfunction "25_25") (pintype "passive"))
    )
    (net (code "264") (name "unconnected-(J5-Pad26)") (class "Default")
      (node (ref "J5") (pin "26") (pinfunction "26_26") (pintype "passive"))
    )
    (net (code "265") (name "unconnected-(J5-Pad29)") (class "Default")
      (node (ref "J5") (pin "29") (pinfunction "29_29") (pintype "passive"))
    )
    (net (code "266") (name "unconnected-(J5-Pad30)") (class "Default")
      (node (ref "J5") (pin "30") (pinfunction "30_30") (pintype "passive"))
    )
    (net (code "267") (name "unconnected-(J9-N.C-Pad7)") (class "Default")
      (node (ref "J9") (pin "7") (pinfunction "N.C_7") (pintype "passive"))
    )
    (net (code "268") (name "unconnected-(J9-Pad13)") (class "Default")
      (node (ref "J9") (pin "13") (pinfunction "13_13") (pintype "passive"))
    )
    (net (code "269") (name "unconnected-(J9-Pad14)") (class "Default")
      (node (ref "J9") (pin "14") (pinfunction "14_14") (pintype "passive"))
    )
    (net (code "270") (name "unconnected-(J9-Pad15)") (class "Default")
      (node (ref "J9") (pin "15") (pinfunction "15_15") (pintype "passive"))
    )
    (net (code "271") (name "unconnected-(J9-Pad16)") (class "Default")
      (node (ref "J9") (pin "16") (pinfunction "16_16") (pintype "passive"))
    )
    (net (code "272") (name "unconnected-(J12-Pad18)") (class "Default")
      (node (ref "J12") (pin "18") (pinfunction "18_18") (pintype "passive"))
    )
    (net (code "273") (name "unconnected-(J14-Pad3)") (class "Default")
      (node (ref "J14") (pin "3") (pinfunction "3_3") (pintype "passive"))
    )
    (net (code "274") (name "unconnected-(J14-Pad4)") (class "Default")
      (node (ref "J14") (pin "4") (pinfunction "4_4") (pintype "passive"))
    )
    (net (code "275") (name "unconnected-(J14-Pad9)") (class "Default")
      (node (ref "J14") (pin "9") (pinfunction "9_9") (pintype "passive"))
    )
    (net (code "276") (name "unconnected-(J14-Pad10)") (class "Default")
      (node (ref "J14") (pin "10") (pinfunction "10_10") (pintype "passive"))
    )
    (net (code "277") (name "unconnected-(J16-Pad3)") (class "Default")
      (node (ref "J16") (pin "3") (pinfunction "3_3") (pintype "passive"))
    )
    (net (code "278") (name "unconnected-(J16-Pad4)") (class "Default")
      (node (ref "J16") (pin "4") (pinfunction "4_4") (pintype "passive"))
    )
    (net (code "279") (name "unconnected-(J16-Pad6)") (class "Default")
      (node (ref "J16") (pin "6") (pinfunction "6_6") (pintype "passive"))
    )
    (net (code "280") (name "unconnected-(J16-Pad8)") (class "Default")
      (node (ref "J16") (pin "8") (pinfunction "8_8") (pintype "passive"))
    )
    (net (code "281") (name "unconnected-(J16-Pad10)") (class "Default")
      (node (ref "J16") (pin "10") (pinfunction "10_10") (pintype "passive"))
    )
    (net (code "282") (name "unconnected-(J18-Pad1)") (class "Default")
      (node (ref "J18") (pin "1") (pinfunction "1_1") (pintype "passive"))
    )
    (net (code "283") (name "unconnected-(J18-Pad2)") (class "Default")
      (node (ref "J18") (pin "2") (pinfunction "2_2") (pintype "passive"))
    )
    (net (code "284") (name "unconnected-(J20-Pad1)") (class "Default")
      (node (ref "J20") (pin "1") (pinfunction "1_1") (pintype "passive"))
    )
    (net (code "285") (name "unconnected-(J20-Pad2)") (class "Default")
      (node (ref "J20") (pin "2") (pinfunction "2_2") (pintype "passive"))
    )
    (net (code "286") (name "unconnected-(J22-Pad1)") (class "Default")
      (node (ref "J22") (pin "1") (pinfunction "1_1") (pintype "passive"))
    )
    (net (code "287") (name "unconnected-(J22-Pad2)") (class "Default")
      (node (ref "J22") (pin "2") (pinfunction "2_2") (pintype "passive"))
    )
    (net (code "288") (name "unconnected-(JC1-Pad3)") (class "Default")
      (node (ref "JC1") (pin "3") (pinfunction "3_3") (pintype "passive"))
    )
    (net (code "289") (name "unconnected-(R84-Pad1)") (class "Default")
      (node (ref "R84") (pin "1") (pinfunction "1_1") (pintype "passive"))
    )
    (net (code "290") (name "unconnected-(U2-EECK-Pad20)") (class "Default")
      (node (ref "U2") (pin "20") (pinfunction "EECK_20") (pintype "passive"))
    )
    (net (code "291") (name "unconnected-(U2-EECS-Pad21)") (class "Default")
      (node (ref "U2") (pin "21") (pinfunction "EECS_21") (pintype "passive"))
    )
    (net (code "292") (name "unconnected-(U2-EEDIO-Pad19)") (class "Default")
      (node (ref "U2") (pin "19") (pinfunction "EEDIO_19") (pintype "passive"))
    )
    (net (code "293") (name "unconnected-(U2-SD-Pad46)") (class "Default")
      (node (ref "U2") (pin "46") (pinfunction "SD_46") (pintype "passive"))
    )
    (net (code "294") (name "unconnected-(U3-ADCLRC{slash}GPIO1-Pad15)") (class "Default")
      (node (ref "U3") (pin "15") (pinfunction "ADCLRC/GPIO1_15") (pintype "passive"))
    )
    (net (code "295") (name "unconnected-(U3-OUT3-Pad30)") (class "Default")
      (node (ref "U3") (pin "30") (pinfunction "OUT3_30") (pintype "passive"))
    )
    (net (code "296") (name "unconnected-(U9-DM1-Pad10)") (class "Default")
      (node (ref "U9") (pin "10") (pinfunction "DM1_10") (pintype "passive"))
    )
    (net (code "297") (name "unconnected-(U9-DM2-Pad8)") (class "Default")
      (node (ref "U9") (pin "8") (pinfunction "DM2_8") (pintype "passive"))
    )
    (net (code "298") (name "unconnected-(U9-DP1-Pad11)") (class "Default")
      (node (ref "U9") (pin "11") (pinfunction "DP1_11") (pintype "passive"))
    )
    (net (code "299") (name "unconnected-(U9-DP2-Pad9)") (class "Default")
      (node (ref "U9") (pin "9") (pinfunction "DP2_9") (pintype "passive"))
    )
    (net (code "300") (name "unconnected-(U9-DRV-Pad22)") (class "Default")
      (node (ref "U9") (pin "22") (pinfunction "DRV_22") (pintype "passive"))
    )
    (net (code "301") (name "unconnected-(U9-LED1-Pad23)") (class "Default")
      (node (ref "U9") (pin "23") (pinfunction "LED1_23") (pintype "passive"))
    )
    (net (code "302") (name "unconnected-(U9-LED2-Pad24)") (class "Default")
      (node (ref "U9") (pin "24") (pinfunction "LED2_24") (pintype "passive"))
    )
    (net (code "303") (name "unconnected-(U9-PWRJ-Pad25)") (class "Default")
      (node (ref "U9") (pin "25") (pinfunction "PWRJ_25") (pintype "passive"))
    )
    (net (code "304") (name "unconnected-(U9-TESTJ-Pad27)") (class "Default")
      (node (ref "U9") (pin "27") (pinfunction "TESTJ_27") (pintype "passive"))
    )
  )
)
